# hackeeg-shield.net
KiCad netlist of a schematic drawn in EAGLE
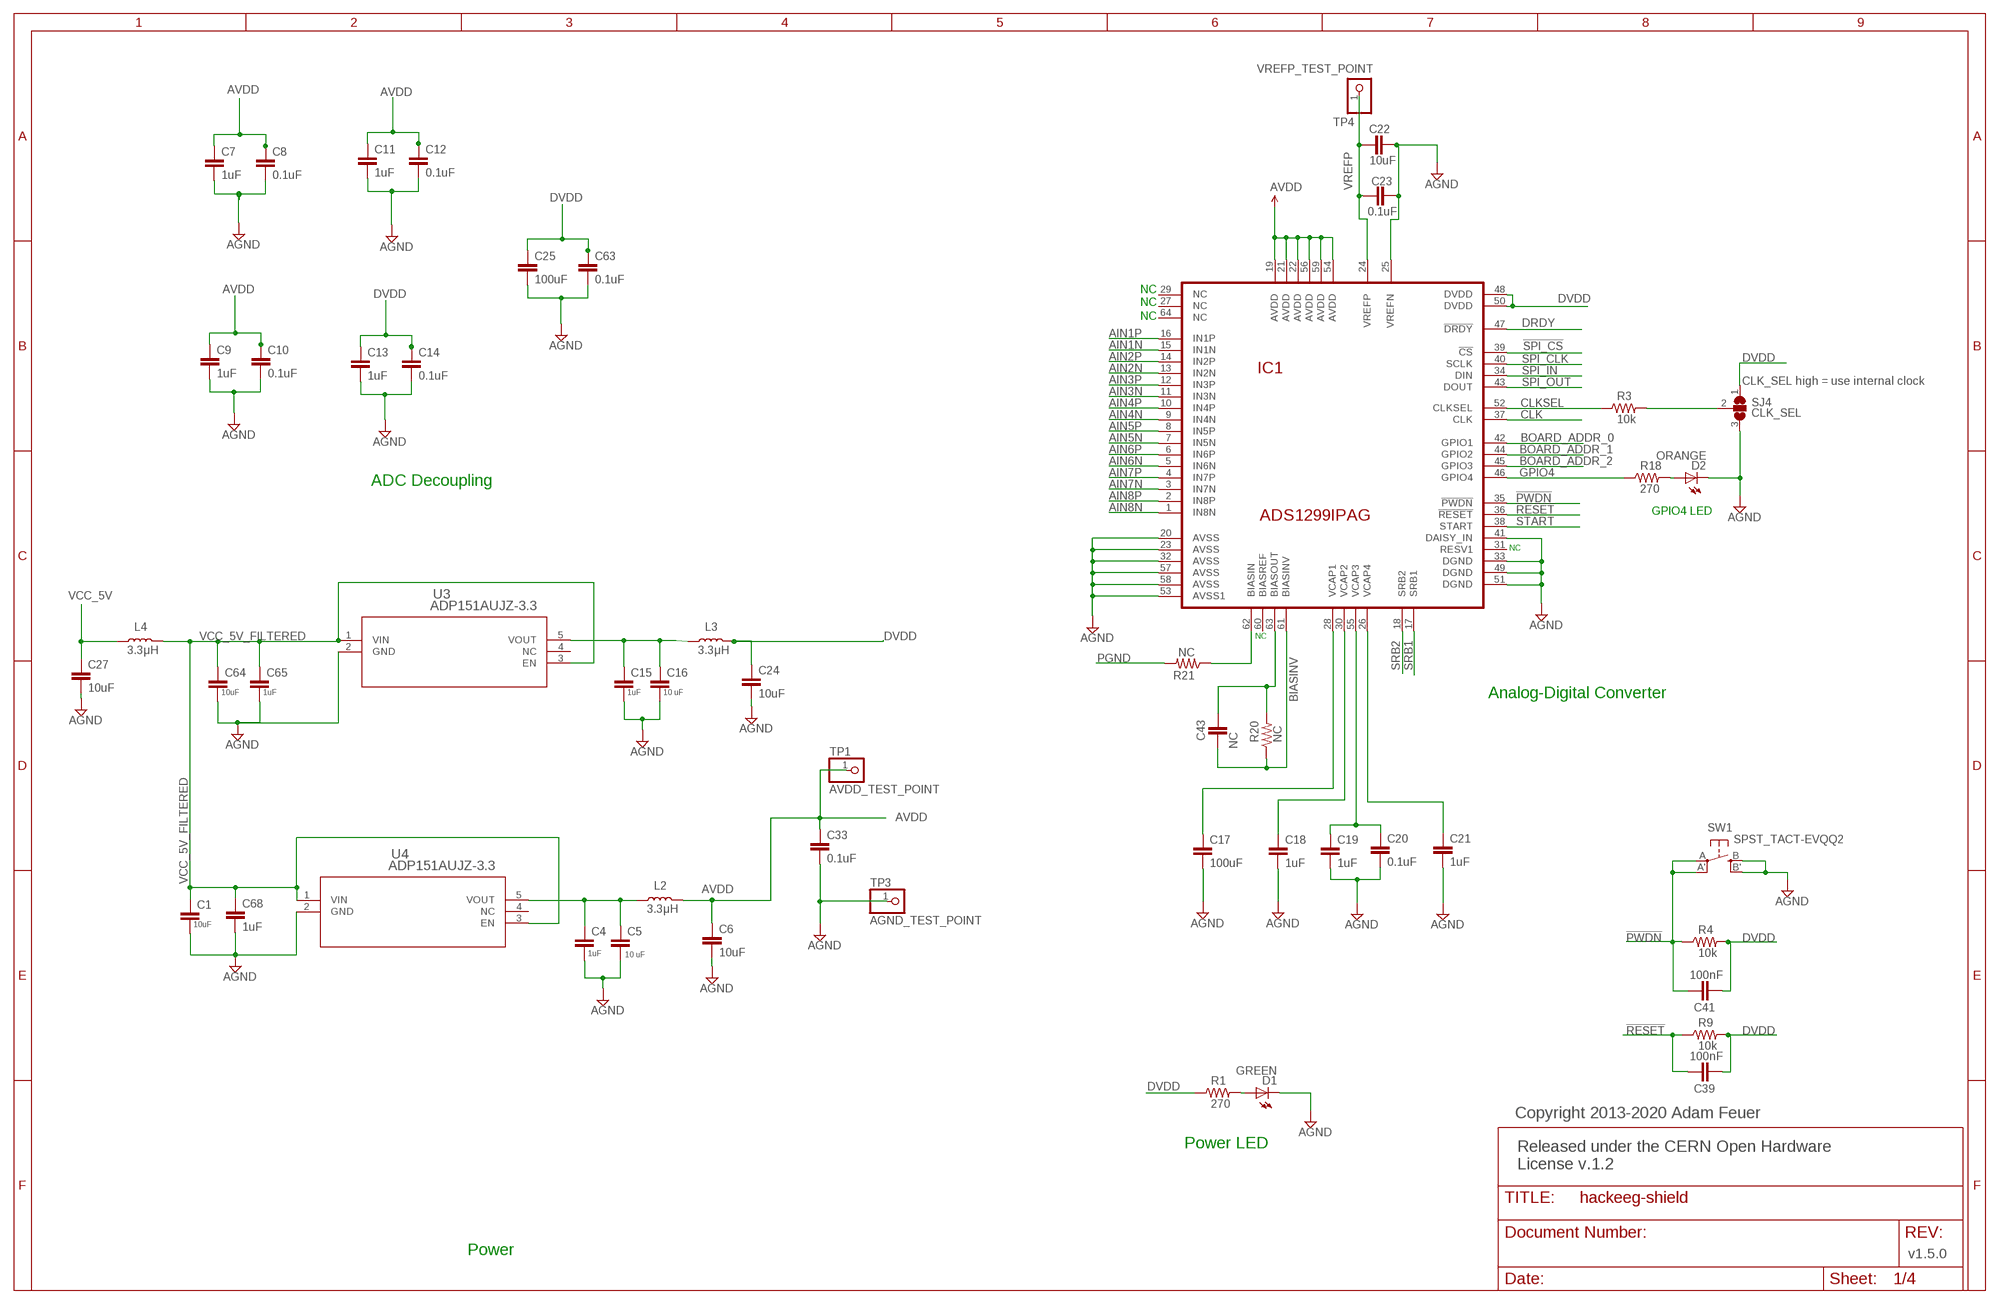
[diagram p0: schematic, sheet 1]
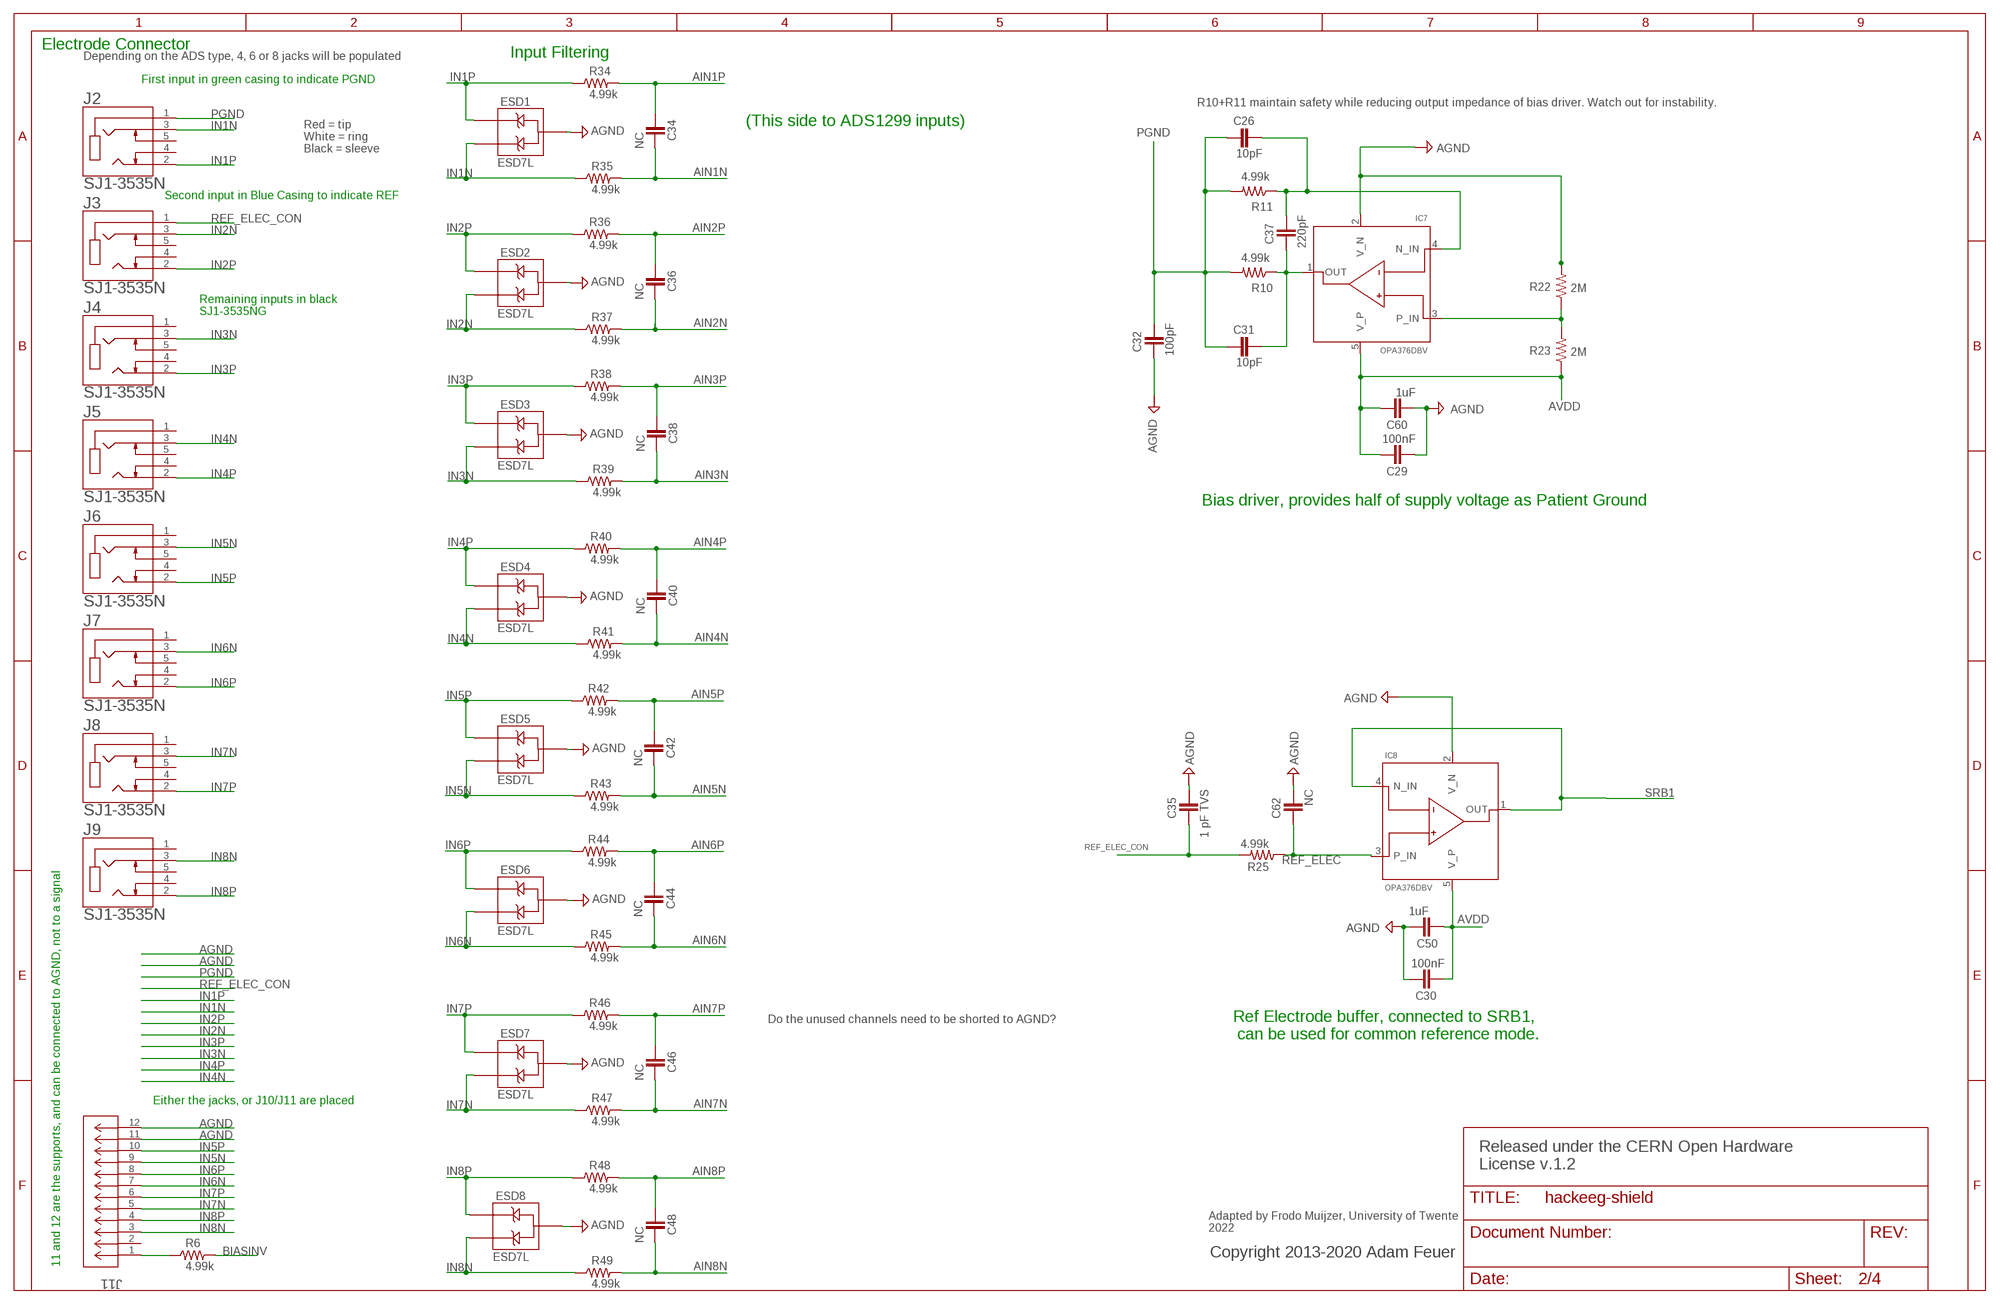
[diagram p1: schematic, sheet 2]
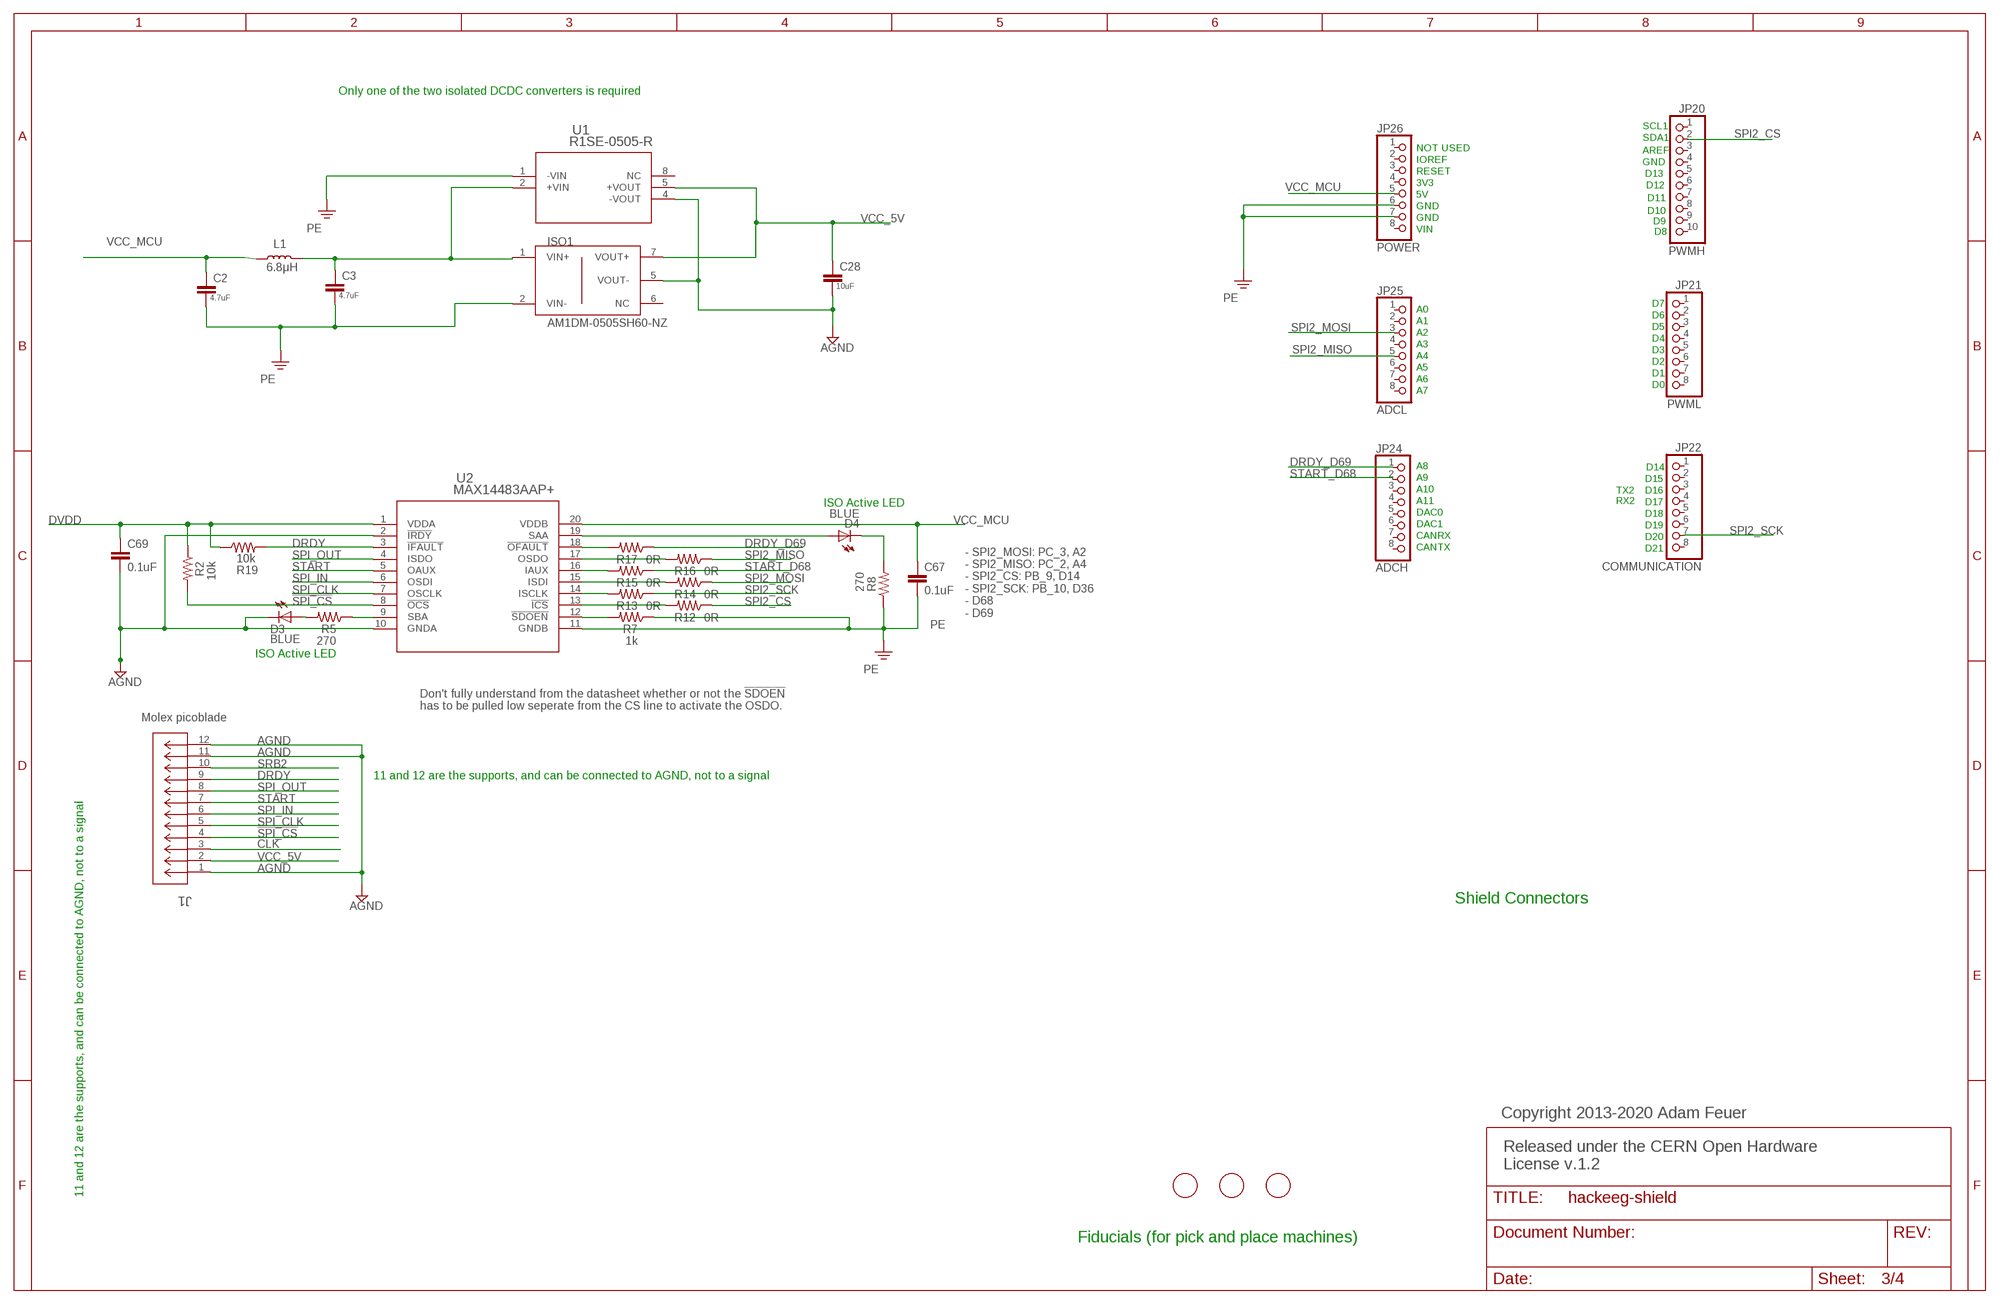
[diagram p2: schematic, sheet 3]
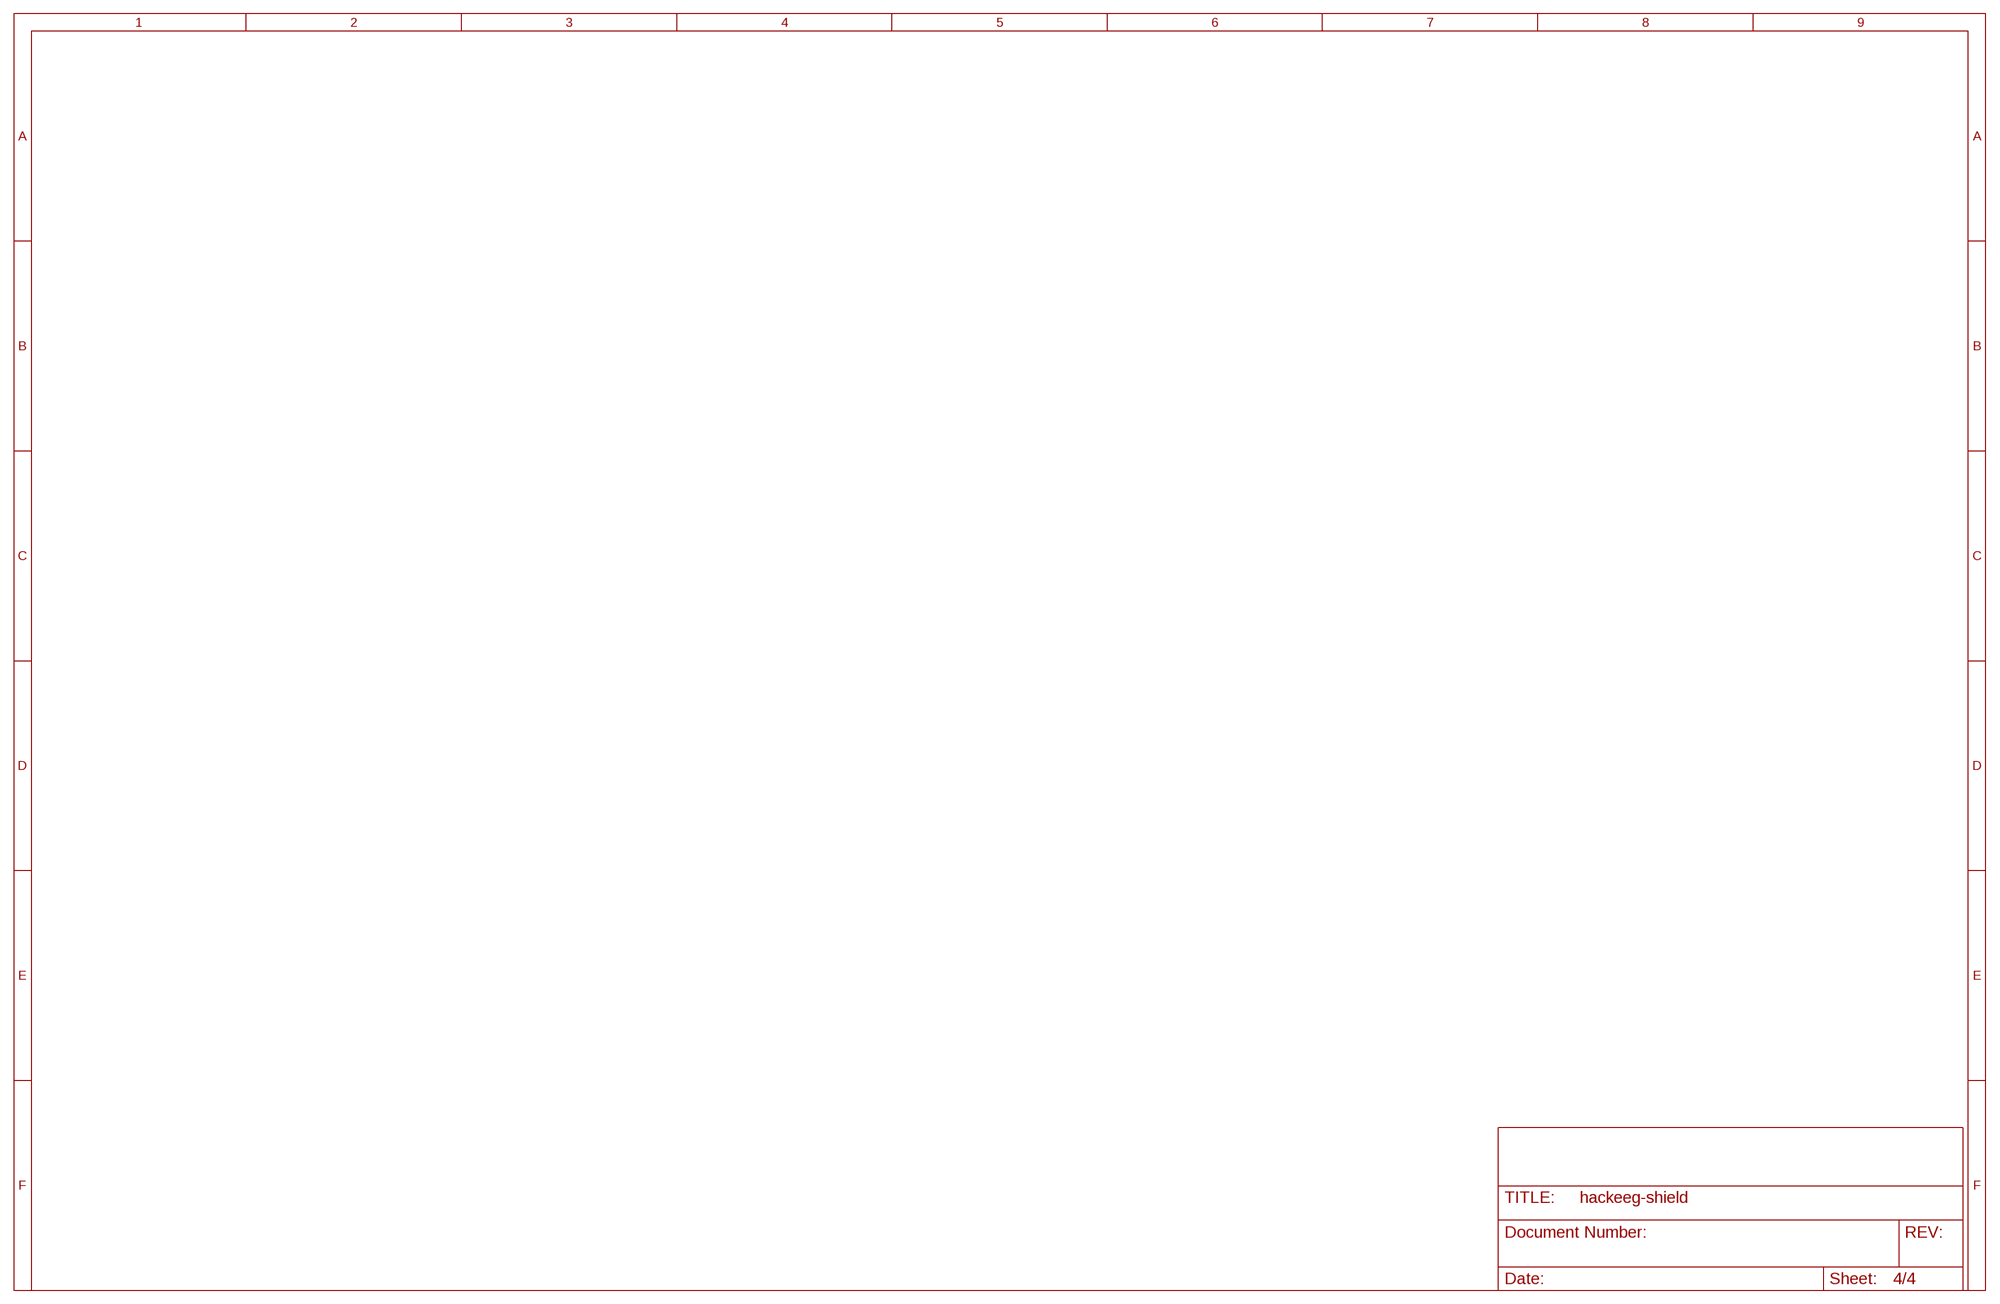
[diagram p3: schematic, sheet 4]

(export (version "E")
  (design (tool "Eeschema 10.0.6"))
  (components
    (comp (ref "C1")
      (value "10uF")
      (footprint "eagle-import:0603-CAP")
      (libsource (lib "eagle-import") (part "CAP0603-CAP"))
    )
    (comp (ref "C4")
      (value "1uF")
      (footprint "eagle-import:0603-CAP")
      (libsource (lib "eagle-import") (part "CAP0603-CAP"))
    )
    (comp (ref "C5")
      (value "10 uF")
      (footprint "eagle-import:0603-CAP")
      (libsource (lib "eagle-import") (part "CAP0603-CAP"))
    )
    (comp (ref "C6")
      (value "10uF")
      (footprint "eagle-import:0603-CAP")
      (libsource (lib "eagle-import") (part "CAP0603-CAP"))
    )
    (comp (ref "C7")
      (value "1uF")
      (footprint "eagle-import:0603-CAP")
      (libsource (lib "eagle-import") (part "CAP0603-CAP"))
    )
    (comp (ref "C8")
      (value "0.1uF")
      (footprint "eagle-import:0603-CAP")
      (libsource (lib "eagle-import") (part "CAP0603-CAP"))
    )
    (comp (ref "C9")
      (value "1uF")
      (footprint "eagle-import:0603-CAP")
      (libsource (lib "eagle-import") (part "CAP0603-CAP"))
    )
    (comp (ref "C10")
      (value "0.1uF")
      (footprint "eagle-import:0603-CAP")
      (libsource (lib "eagle-import") (part "CAP0603-CAP"))
    )
    (comp (ref "C11")
      (value "1uF")
      (footprint "eagle-import:0603-CAP")
      (libsource (lib "eagle-import") (part "CAP0603-CAP"))
    )
    (comp (ref "C12")
      (value "0.1uF")
      (footprint "eagle-import:0603-CAP")
      (libsource (lib "eagle-import") (part "CAP0603-CAP"))
    )
    (comp (ref "C13")
      (value "1uF")
      (footprint "eagle-import:0603-CAP")
      (libsource (lib "eagle-import") (part "CAP0603-CAP"))
    )
    (comp (ref "C14")
      (value "0.1uF")
      (footprint "eagle-import:0603-CAP")
      (libsource (lib "eagle-import") (part "CAP0603-CAP"))
    )
    (comp (ref "C15")
      (value "1uF")
      (footprint "eagle-import:0603-CAP")
      (libsource (lib "eagle-import") (part "CAP0603-CAP"))
    )
    (comp (ref "C16")
      (value "10 uF")
      (footprint "eagle-import:0603-CAP")
      (libsource (lib "eagle-import") (part "CAP0603-CAP"))
    )
    (comp (ref "C17")
      (value "100uF")
      (footprint "eagle-import:1210")
      (libsource (lib "eagle-import") (part "CAP1210"))
    )
    (comp (ref "C18")
      (value "1uF")
      (footprint "eagle-import:0603-CAP")
      (libsource (lib "eagle-import") (part "CAP0603-CAP"))
    )
    (comp (ref "C19")
      (value "1uF")
      (footprint "eagle-import:0603-CAP")
      (libsource (lib "eagle-import") (part "CAP0603-CAP"))
    )
    (comp (ref "C20")
      (value "0.1uF")
      (footprint "eagle-import:0603-CAP")
      (libsource (lib "eagle-import") (part "CAP0603-CAP"))
    )
    (comp (ref "C21")
      (value "1uF")
      (footprint "eagle-import:0603-CAP")
      (libsource (lib "eagle-import") (part "CAP0603-CAP"))
    )
    (comp (ref "C22")
      (value "10uF")
      (footprint "eagle-import:0603-CAP")
      (libsource (lib "eagle-import") (part "CAP0603-CAP"))
    )
    (comp (ref "C23")
      (value "0.1uF")
      (footprint "eagle-import:0603-CAP")
      (libsource (lib "eagle-import") (part "CAP0603-CAP"))
    )
    (comp (ref "C24")
      (value "10uF")
      (footprint "eagle-import:0603-CAP")
      (libsource (lib "eagle-import") (part "CAP0603-CAP"))
    )
    (comp (ref "C25")
      (value "100uF")
      (footprint "eagle-import:1210")
      (libsource (lib "eagle-import") (part "CAP1210"))
    )
    (comp (ref "C27")
      (value "10uF")
      (footprint "eagle-import:0603-CAP")
      (libsource (lib "eagle-import") (part "CAP0603-CAP"))
    )
    (comp (ref "C33")
      (value "0.1uF")
      (footprint "eagle-import:0603-CAP")
      (libsource (lib "eagle-import") (part "CAP0603-CAP"))
    )
    (comp (ref "C39")
      (value "100nF")
      (footprint "eagle-import:0603-CAP")
      (libsource (lib "eagle-import") (part "CAP0603-CAP"))
    )
    (comp (ref "C41")
      (value "100nF")
      (footprint "eagle-import:0603-CAP")
      (libsource (lib "eagle-import") (part "CAP0603-CAP"))
    )
    (comp (ref "C43")
      (value "NC")
      (footprint "eagle-import:0603-CAP")
      (libsource (lib "eagle-import") (part "CAP0603-CAP"))
    )
    (comp (ref "C63")
      (value "0.1uF")
      (footprint "eagle-import:0603-CAP")
      (libsource (lib "eagle-import") (part "CAP0603-CAP"))
    )
    (comp (ref "C64")
      (value "10uF")
      (footprint "eagle-import:0603-CAP")
      (libsource (lib "eagle-import") (part "CAP0603-CAP"))
    )
    (comp (ref "C65")
      (value "1uF")
      (footprint "eagle-import:0603-CAP")
      (libsource (lib "eagle-import") (part "CAP0603-CAP"))
    )
    (comp (ref "C68")
      (value "1uF")
      (footprint "eagle-import:0603-CAP")
      (libsource (lib "eagle-import") (part "CAP0603-CAP"))
    )
    (comp (ref "D1")
      (value "GREEN")
      (footprint "eagle-import:LED-1206")
      (libsource (lib "eagle-import") (part "LED-RED1206"))
    )
    (comp (ref "D2")
      (value "ORANGE")
      (footprint "eagle-import:LED-1206")
      (libsource (lib "eagle-import") (part "LED-WHITE"))
    )
    (comp (ref "IC1")
      (value "ADS1299IPAG")
      (footprint "eagle-import:TQFP64")
      (libsource (lib "eagle-import") (part "ADS1299PAG"))
    )
    (comp (ref "L2")
      (value "3.3μH")
      (footprint "eagle-import:0805-WIDE")
      (libsource (lib "eagle-import") (part "1.0μH-0805_WIDE-1.0μH-1.4A-0.07OHM-1.4MM_H"))
    )
    (comp (ref "L3")
      (value "3.3μH")
      (footprint "eagle-import:0805-WIDE")
      (libsource (lib "eagle-import") (part "1.0μH-0805_WIDE-1.0μH-1.4A-0.07OHM-1.4MM_H"))
    )
    (comp (ref "L4")
      (value "3.3μH")
      (footprint "eagle-import:0805-WIDE")
      (libsource (lib "eagle-import") (part "1.0μH-0805_WIDE-1.0μH-1.4A-0.07OHM-1.4MM_H"))
    )
    (comp (ref "R1")
      (value "270")
      (footprint "eagle-import:0603-RES")
      (libsource (lib "eagle-import") (part "RESISTOR0603-RES"))
    )
    (comp (ref "R3")
      (value "10k")
      (footprint "eagle-import:0603-RES")
      (libsource (lib "eagle-import") (part "RESISTOR0603-RES"))
    )
    (comp (ref "R4")
      (value "10k")
      (footprint "eagle-import:0603-RES")
      (libsource (lib "eagle-import") (part "RESISTOR0603-RES"))
    )
    (comp (ref "R9")
      (value "10k")
      (footprint "eagle-import:0603-RES")
      (libsource (lib "eagle-import") (part "RESISTOR0603-RES"))
    )
    (comp (ref "R18")
      (value "270")
      (footprint "eagle-import:0603-RES")
      (libsource (lib "eagle-import") (part "RESISTOR0603-RES"))
    )
    (comp (ref "R20")
      (value "NC")
      (footprint "eagle-import:0603-RES")
      (libsource (lib "eagle-import") (part "RESISTOR0603-RES"))
    )
    (comp (ref "R21")
      (value "NC")
      (footprint "eagle-import:0603-RES")
      (libsource (lib "eagle-import") (part "RESISTOR0603-RES"))
    )
    (comp (ref "SJ4")
      (value "CLK_SEL")
      (footprint "eagle-import:SJ_2")
      (libsource (lib "eagle-import") (part "SJ2W"))
    )
    (comp (ref "SW1")
      (value "SPST_TACT-EVQQ2")
      (footprint "eagle-import:EVQ-Q2")
      (libsource (lib "eagle-import") (part "SPST_TACT-EVQQ2"))
    )
    (comp (ref "TP1")
      (value "AVDD_TEST_POINT")
      (footprint "eagle-import:1X01")
      (libsource (lib "eagle-import") (part "PINHD-1X1"))
    )
    (comp (ref "TP3")
      (value "AGND_TEST_POINT")
      (footprint "eagle-import:1X01")
      (libsource (lib "eagle-import") (part "PINHD-1X1"))
    )
    (comp (ref "TP4")
      (value "VREFP_TEST_POINT")
      (footprint "eagle-import:1X01")
      (libsource (lib "eagle-import") (part "PINHD-1X1"))
    )
    (comp (ref "U3")
      (value "ADP151AUJZ-3.3")
      (footprint "eagle-import:UJ_5_ADI")
      (fields
        (field (name "MANUFACTURER_PART_NUMBER") "ADP151AUJZ-1.2-R7")
        (field (name "COPYRIGHT") "Copyright (C) 2022 Ultra Librarian. All rights reserved.")
      )
      (libsource (lib "eagle-import") (part "ADP151AUJZ-3.3"))
    )
    (comp (ref "U4")
      (value "ADP151AUJZ-3.3")
      (footprint "eagle-import:UJ_5_ADI")
      (fields
        (field (name "MANUFACTURER_PART_NUMBER") "ADP151AUJZ-1.2-R7")
        (field (name "COPYRIGHT") "Copyright (C) 2022 Ultra Librarian. All rights reserved.")
      )
      (libsource (lib "eagle-import") (part "ADP151AUJZ-3.3"))
    )
    (comp (ref "C26")
      (value "10pF")
      (footprint "eagle-import:0603-CAP")
      (libsource (lib "eagle-import") (part "CAP0603-CAP"))
    )
    (comp (ref "C29")
      (value "100nF")
      (footprint "eagle-import:0603-CAP")
      (libsource (lib "eagle-import") (part "CAP0603-CAP"))
    )
    (comp (ref "C30")
      (value "100nF")
      (footprint "eagle-import:0603-CAP")
      (libsource (lib "eagle-import") (part "CAP0603-CAP"))
    )
    (comp (ref "C31")
      (value "10pF")
      (footprint "eagle-import:0603-CAP")
      (libsource (lib "eagle-import") (part "CAP0603-CAP"))
    )
    (comp (ref "C32")
      (value "100pF")
      (footprint "eagle-import:0603-CAP")
      (libsource (lib "eagle-import") (part "CAP0603-CAP"))
    )
    (comp (ref "C34")
      (value "NC")
      (footprint "eagle-import:0603-CAP")
      (libsource (lib "eagle-import") (part "CAP0603-CAP"))
    )
    (comp (ref "C35")
      (value "1 pF TVS")
      (footprint "eagle-import:0603-CAP")
      (libsource (lib "eagle-import") (part "CAP0603-CAP"))
    )
    (comp (ref "C36")
      (value "NC")
      (footprint "eagle-import:0603-CAP")
      (libsource (lib "eagle-import") (part "CAP0603-CAP"))
    )
    (comp (ref "C37")
      (value "220pF")
      (footprint "eagle-import:0603-CAP")
      (libsource (lib "eagle-import") (part "CAP0603-CAP"))
    )
    (comp (ref "C38")
      (value "NC")
      (footprint "eagle-import:0603-CAP")
      (libsource (lib "eagle-import") (part "CAP0603-CAP"))
    )
    (comp (ref "C40")
      (value "NC")
      (footprint "eagle-import:0603-CAP")
      (libsource (lib "eagle-import") (part "CAP0603-CAP"))
    )
    (comp (ref "C42")
      (value "NC")
      (footprint "eagle-import:0603-CAP")
      (libsource (lib "eagle-import") (part "CAP0603-CAP"))
    )
    (comp (ref "C44")
      (value "NC")
      (footprint "eagle-import:0603-CAP")
      (libsource (lib "eagle-import") (part "CAP0603-CAP"))
    )
    (comp (ref "C46")
      (value "NC")
      (footprint "eagle-import:0603-CAP")
      (libsource (lib "eagle-import") (part "CAP0603-CAP"))
    )
    (comp (ref "C48")
      (value "NC")
      (footprint "eagle-import:0603-CAP")
      (libsource (lib "eagle-import") (part "CAP0603-CAP"))
    )
    (comp (ref "C50")
      (value "1uF")
      (footprint "eagle-import:0603-CAP")
      (libsource (lib "eagle-import") (part "CAP0603-CAP"))
    )
    (comp (ref "C60")
      (value "1uF")
      (footprint "eagle-import:0603-CAP")
      (libsource (lib "eagle-import") (part "CAP0603-CAP"))
    )
    (comp (ref "C62")
      (value "NC")
      (footprint "eagle-import:0603-CAP")
      (libsource (lib "eagle-import") (part "CAP0603-CAP"))
    )
    (comp (ref "ESD1")
      (value "ESD7L")
      (footprint "eagle-import:SOT-723")
      (fields (field (name "MF") "ON Semiconductor"))
      (libsource (lib "eagle-import") (part "ESD7L"))
    )
    (comp (ref "ESD2")
      (value "ESD7L")
      (footprint "eagle-import:SOT-723")
      (fields (field (name "MF") "ON Semiconductor"))
      (libsource (lib "eagle-import") (part "ESD7L"))
    )
    (comp (ref "ESD3")
      (value "ESD7L")
      (footprint "eagle-import:SOT-723")
      (fields (field (name "MF") "ON Semiconductor"))
      (libsource (lib "eagle-import") (part "ESD7L"))
    )
    (comp (ref "ESD4")
      (value "ESD7L")
      (footprint "eagle-import:SOT-723")
      (fields (field (name "MF") "ON Semiconductor"))
      (libsource (lib "eagle-import") (part "ESD7L"))
    )
    (comp (ref "ESD5")
      (value "ESD7L")
      (footprint "eagle-import:SOT-723")
      (fields (field (name "MF") "ON Semiconductor"))
      (libsource (lib "eagle-import") (part "ESD7L"))
    )
    (comp (ref "ESD6")
      (value "ESD7L")
      (footprint "eagle-import:SOT-723")
      (fields (field (name "MF") "ON Semiconductor"))
      (libsource (lib "eagle-import") (part "ESD7L"))
    )
    (comp (ref "ESD7")
      (value "ESD7L")
      (footprint "eagle-import:SOT-723")
      (fields (field (name "MF") "ON Semiconductor"))
      (libsource (lib "eagle-import") (part "ESD7L"))
    )
    (comp (ref "ESD8")
      (value "ESD7L")
      (footprint "eagle-import:SOT-723")
      (fields (field (name "MF") "ON Semiconductor"))
      (libsource (lib "eagle-import") (part "ESD7L"))
    )
    (comp (ref "IC7")
      (value "OPA376DBV")
      (footprint "eagle-import:SOT23-5")
      (libsource (lib "eagle-import") (part "OPA376DBV"))
    )
    (comp (ref "IC8")
      (value "OPA376DBV")
      (footprint "eagle-import:SOT23-5")
      (libsource (lib "eagle-import") (part "OPA376DBV"))
    )
    (comp (ref "J2")
      (value "SJ1-3535N")
      (footprint "eagle-import:CUI_SJ1-3535N")
      (fields (field (name "MANUFACTURER") "CUI"))
      (libsource (lib "eagle-import") (part "SJ1-3535N"))
    )
    (comp (ref "J3")
      (value "SJ1-3535N")
      (footprint "eagle-import:CUI_SJ1-3535N")
      (fields (field (name "MANUFACTURER") "CUI"))
      (libsource (lib "eagle-import") (part "SJ1-3535N"))
    )
    (comp (ref "J4")
      (value "SJ1-3535N")
      (footprint "eagle-import:CUI_SJ1-3535N")
      (fields (field (name "MANUFACTURER") "CUI"))
      (libsource (lib "eagle-import") (part "SJ1-3535N"))
    )
    (comp (ref "J5")
      (value "SJ1-3535N")
      (footprint "eagle-import:CUI_SJ1-3535N")
      (fields (field (name "MANUFACTURER") "CUI"))
      (libsource (lib "eagle-import") (part "SJ1-3535N"))
    )
    (comp (ref "J6")
      (value "SJ1-3535N")
      (footprint "eagle-import:CUI_SJ1-3535N")
      (fields (field (name "MANUFACTURER") "CUI"))
      (libsource (lib "eagle-import") (part "SJ1-3535N"))
    )
    (comp (ref "J7")
      (value "SJ1-3535N")
      (footprint "eagle-import:CUI_SJ1-3535N")
      (fields (field (name "MANUFACTURER") "CUI"))
      (libsource (lib "eagle-import") (part "SJ1-3535N"))
    )
    (comp (ref "J8")
      (value "SJ1-3535N")
      (footprint "eagle-import:CUI_SJ1-3535N")
      (fields (field (name "MANUFACTURER") "CUI"))
      (libsource (lib "eagle-import") (part "SJ1-3535N"))
    )
    (comp (ref "J9")
      (value "SJ1-3535N")
      (footprint "eagle-import:CUI_SJ1-3535N")
      (fields (field (name "MANUFACTURER") "CUI"))
      (libsource (lib "eagle-import") (part "SJ1-3535N"))
    )
    (comp (ref "J11")
      (value "533981071")
      (footprint "eagle-import:CON_533981071")
      (fields (field (name "COPYRIGHT") "Copyright (C) 2022 Ultra Librarian. All rights reserved."))
      (libsource (lib "eagle-import") (part "533981071"))
    )
    (comp (ref "R6")
      (value "4.99k")
      (footprint "eagle-import:0603-RES")
      (libsource (lib "eagle-import") (part "RESISTOR0603-RES"))
    )
    (comp (ref "R10")
      (value "4.99k")
      (footprint "eagle-import:0603-RES")
      (libsource (lib "eagle-import") (part "RESISTOR0603-RES"))
    )
    (comp (ref "R11")
      (value "4.99k")
      (footprint "eagle-import:0603-RES")
      (libsource (lib "eagle-import") (part "RESISTOR0603-RES"))
    )
    (comp (ref "R22")
      (value "2M")
      (footprint "eagle-import:0603-RES")
      (libsource (lib "eagle-import") (part "RESISTOR0603-RES"))
    )
    (comp (ref "R23")
      (value "2M")
      (footprint "eagle-import:0603-RES")
      (libsource (lib "eagle-import") (part "RESISTOR0603-RES"))
    )
    (comp (ref "R25")
      (value "4.99k")
      (footprint "eagle-import:0603-RES")
      (libsource (lib "eagle-import") (part "RESISTOR0603-RES"))
    )
    (comp (ref "R34")
      (value "4.99k")
      (footprint "eagle-import:0603-RES")
      (libsource (lib "eagle-import") (part "RESISTOR0603-RES"))
    )
    (comp (ref "R35")
      (value "4.99k")
      (footprint "eagle-import:0603-RES")
      (libsource (lib "eagle-import") (part "RESISTOR0603-RES"))
    )
    (comp (ref "R36")
      (value "4.99k")
      (footprint "eagle-import:0603-RES")
      (libsource (lib "eagle-import") (part "RESISTOR0603-RES"))
    )
    (comp (ref "R37")
      (value "4.99k")
      (footprint "eagle-import:0603-RES")
      (libsource (lib "eagle-import") (part "RESISTOR0603-RES"))
    )
    (comp (ref "R38")
      (value "4.99k")
      (footprint "eagle-import:0603-RES")
      (libsource (lib "eagle-import") (part "RESISTOR0603-RES"))
    )
    (comp (ref "R39")
      (value "4.99k")
      (footprint "eagle-import:0603-RES")
      (libsource (lib "eagle-import") (part "RESISTOR0603-RES"))
    )
    (comp (ref "R40")
      (value "4.99k")
      (footprint "eagle-import:0603-RES")
      (libsource (lib "eagle-import") (part "RESISTOR0603-RES"))
    )
    (comp (ref "R41")
      (value "4.99k")
      (footprint "eagle-import:0603-RES")
      (libsource (lib "eagle-import") (part "RESISTOR0603-RES"))
    )
    (comp (ref "R42")
      (value "4.99k")
      (footprint "eagle-import:0603-RES")
      (libsource (lib "eagle-import") (part "RESISTOR0603-RES"))
    )
    (comp (ref "R43")
      (value "4.99k")
      (footprint "eagle-import:0603-RES")
      (libsource (lib "eagle-import") (part "RESISTOR0603-RES"))
    )
    (comp (ref "R44")
      (value "4.99k")
      (footprint "eagle-import:0603-RES")
      (libsource (lib "eagle-import") (part "RESISTOR0603-RES"))
    )
    (comp (ref "R45")
      (value "4.99k")
      (footprint "eagle-import:0603-RES")
      (libsource (lib "eagle-import") (part "RESISTOR0603-RES"))
    )
    (comp (ref "R46")
      (value "4.99k")
      (footprint "eagle-import:0603-RES")
      (libsource (lib "eagle-import") (part "RESISTOR0603-RES"))
    )
    (comp (ref "R47")
      (value "4.99k")
      (footprint "eagle-import:0603-RES")
      (libsource (lib "eagle-import") (part "RESISTOR0603-RES"))
    )
    (comp (ref "R48")
      (value "4.99k")
      (footprint "eagle-import:0603-RES")
      (libsource (lib "eagle-import") (part "RESISTOR0603-RES"))
    )
    (comp (ref "R49")
      (value "4.99k")
      (footprint "eagle-import:0603-RES")
      (libsource (lib "eagle-import") (part "RESISTOR0603-RES"))
    )
    (comp (ref "C2")
      (value "4.7uF")
      (footprint "eagle-import:0603-CAP")
      (libsource (lib "eagle-import") (part "CAP0603-CAP"))
    )
    (comp (ref "C3")
      (value "4.7uF")
      (footprint "eagle-import:0603-CAP")
      (libsource (lib "eagle-import") (part "CAP0603-CAP"))
    )
    (comp (ref "C28")
      (value "10uF")
      (footprint "eagle-import:0603-CAP")
      (libsource (lib "eagle-import") (part "CAP0603-CAP"))
    )
    (comp (ref "C67")
      (value "0.1uF")
      (footprint "eagle-import:0603-CAP")
      (libsource (lib "eagle-import") (part "CAP0603-CAP"))
    )
    (comp (ref "C69")
      (value "0.1uF")
      (footprint "eagle-import:0603-CAP")
      (libsource (lib "eagle-import") (part "CAP0603-CAP"))
    )
    (comp (ref "D3")
      (value "BLUE")
      (footprint "eagle-import:LED-1206")
      (libsource (lib "eagle-import") (part "LED-WHITE"))
    )
    (comp (ref "D4")
      (value "BLUE")
      (footprint "eagle-import:LED-1206")
      (libsource (lib "eagle-import") (part "LED-WHITE"))
    )
    (comp (ref "ISO1")
      (value "AM1DM-0505SH60-NZ")
      (footprint "eagle-import:SIP1005W50P254L1965H1265Q7")
      (libsource (lib "eagle-import") (part "AM1DM-0505SH60-NZ"))
    )
    (comp (ref "J1")
      (value "533981071")
      (footprint "eagle-import:CON_533981071")
      (fields (field (name "COPYRIGHT") "Copyright (C) 2022 Ultra Librarian. All rights reserved."))
      (libsource (lib "eagle-import") (part "533981071"))
    )
    (comp (ref "JP20")
      (value "PWMH")
      (footprint "eagle-import:1X10")
      (libsource (lib "eagle-import") (part "PINHD-1X10"))
    )
    (comp (ref "JP21")
      (value "PWML")
      (footprint "eagle-import:1X08")
      (libsource (lib "eagle-import") (part "PINHD-1X8"))
    )
    (comp (ref "JP22")
      (value "COMMUNICATION")
      (footprint "eagle-import:1X08")
      (libsource (lib "eagle-import") (part "PINHD-1X8"))
    )
    (comp (ref "JP24")
      (value "ADCH")
      (footprint "eagle-import:1X08")
      (libsource (lib "eagle-import") (part "PINHD-1X8"))
    )
    (comp (ref "JP25")
      (value "ADCL")
      (footprint "eagle-import:1X08")
      (libsource (lib "eagle-import") (part "PINHD-1X8"))
    )
    (comp (ref "JP26")
      (value "POWER")
      (footprint "eagle-import:1X08")
      (libsource (lib "eagle-import") (part "PINHD-1X8"))
    )
    (comp (ref "L1")
      (value "6.8μH")
      (footprint "eagle-import:0805-WIDE")
      (fields (field (name "SPICEPREFIX") "L"))
      (libsource (lib "eagle-import") (part "1.0μH-0805_WIDE-1.0μH-1.4A-0.07OHM-1.4MM_H"))
    )
    (comp (ref "R2")
      (value "10k")
      (footprint "eagle-import:0603-RES")
      (libsource (lib "eagle-import") (part "RESISTOR0603-RES"))
    )
    (comp (ref "R5")
      (value "270")
      (footprint "eagle-import:0603-RES")
      (libsource (lib "eagle-import") (part "RESISTOR0603-RES"))
    )
    (comp (ref "R7")
      (value "1k")
      (footprint "eagle-import:0603-RES")
      (libsource (lib "eagle-import") (part "RESISTOR0603-RES"))
    )
    (comp (ref "R8")
      (value "270")
      (footprint "eagle-import:0603-RES")
      (libsource (lib "eagle-import") (part "RESISTOR0603-RES"))
    )
    (comp (ref "R12")
      (value "0R")
      (footprint "eagle-import:0603-RES")
      (libsource (lib "eagle-import") (part "RESISTOR0603-RES"))
    )
    (comp (ref "R13")
      (value "0R")
      (footprint "eagle-import:0603-RES")
      (libsource (lib "eagle-import") (part "RESISTOR0603-RES"))
    )
    (comp (ref "R14")
      (value "0R")
      (footprint "eagle-import:0603-RES")
      (libsource (lib "eagle-import") (part "RESISTOR0603-RES"))
    )
    (comp (ref "R15")
      (value "0R")
      (footprint "eagle-import:0603-RES")
      (libsource (lib "eagle-import") (part "RESISTOR0603-RES"))
    )
    (comp (ref "R16")
      (value "0R")
      (footprint "eagle-import:0603-RES")
      (libsource (lib "eagle-import") (part "RESISTOR0603-RES"))
    )
    (comp (ref "R17")
      (value "0R")
      (footprint "eagle-import:0603-RES")
      (libsource (lib "eagle-import") (part "RESISTOR0603-RES"))
    )
    (comp (ref "R19")
      (value "10k")
      (footprint "eagle-import:0603-RES")
      (libsource (lib "eagle-import") (part "RESISTOR0603-RES"))
    )
    (comp (ref "U$2")
      (value "FIDUCIAL")
      (footprint "eagle-import:FIDUCIAL_1MM")
      (libsource (lib "eagle-import") (part "FIDUCIAL"))
    )
    (comp (ref "U$5")
      (value "FIDUCIAL")
      (footprint "eagle-import:FIDUCIAL_1MM")
      (libsource (lib "eagle-import") (part "FIDUCIAL"))
    )
    (comp (ref "U$6")
      (value "FIDUCIAL")
      (footprint "eagle-import:FIDUCIAL_1MM")
      (libsource (lib "eagle-import") (part "FIDUCIAL"))
    )
    (comp (ref "U1")
      (value "R1SE-0505-R")
      (footprint "eagle-import:R1SE-0505-R_RCP")
      (fields (field (name "COPYRIGHT") "Copyright (C) 2022 Ultra Librarian. All rights reserved."))
      (libsource (lib "eagle-import") (part "R1SE-0505-R"))
    )
    (comp (ref "U2")
      (value "MAX14483AAP+")
      (footprint "eagle-import:21-0056C_20_MXM")
      (fields (field (name "COPYRIGHT") "Copyright (C) 2022 Ultra Librarian. All rights reserved."))
      (libsource (lib "eagle-import") (part "MAX14483AAP+"))
    )
  )
  (nets
    (net (code "1") (name "AGND") (class "Default")
      (node (ref "C1") (pin "2") (pinfunction "2_2") (pintype "passive"))
      (node (ref "C10") (pin "2") (pinfunction "2_2") (pintype "passive"))
      (node (ref "C11") (pin "2") (pinfunction "2_2") (pintype "passive"))
      (node (ref "C12") (pin "2") (pinfunction "2_2") (pintype "passive"))
      (node (ref "C13") (pin "2") (pinfunction "2_2") (pintype "passive"))
      (node (ref "C14") (pin "2") (pinfunction "2_2") (pintype "passive"))
      (node (ref "C15") (pin "2") (pinfunction "2_2") (pintype "passive"))
      (node (ref "C16") (pin "2") (pinfunction "2_2") (pintype "passive"))
      (node (ref "C17") (pin "2") (pinfunction "2_2") (pintype "passive"))
      (node (ref "C18") (pin "2") (pinfunction "2_2") (pintype "passive"))
      (node (ref "C19") (pin "2") (pinfunction "2_2") (pintype "passive"))
      (node (ref "C20") (pin "2") (pinfunction "2_2") (pintype "passive"))
      (node (ref "C21") (pin "2") (pinfunction "2_2") (pintype "passive"))
      (node (ref "C22") (pin "2") (pinfunction "2_2") (pintype "passive"))
      (node (ref "C23") (pin "2") (pinfunction "2_2") (pintype "passive"))
      (node (ref "C24") (pin "2") (pinfunction "2_2") (pintype "passive"))
      (node (ref "C25") (pin "2") (pinfunction "2_2") (pintype "passive"))
      (node (ref "C27") (pin "2") (pinfunction "2_2") (pintype "passive"))
      (node (ref "C28") (pin "2") (pinfunction "2_2") (pintype "passive"))
      (node (ref "C29") (pin "2") (pinfunction "2_2") (pintype "passive"))
      (node (ref "C30") (pin "1") (pinfunction "1_1") (pintype "passive"))
      (node (ref "C32") (pin "1") (pinfunction "1_1") (pintype "passive"))
      (node (ref "C33") (pin "2") (pinfunction "2_2") (pintype "passive"))
      (node (ref "C35") (pin "2") (pinfunction "2_2") (pintype "passive"))
      (node (ref "C4") (pin "2") (pinfunction "2_2") (pintype "passive"))
      (node (ref "C5") (pin "2") (pinfunction "2_2") (pintype "passive"))
      (node (ref "C50") (pin "2") (pinfunction "2_2") (pintype "passive"))
      (node (ref "C6") (pin "2") (pinfunction "2_2") (pintype "passive"))
      (node (ref "C60") (pin "2") (pinfunction "2_2") (pintype "passive"))
      (node (ref "C62") (pin "2") (pinfunction "2_2") (pintype "passive"))
      (node (ref "C63") (pin "2") (pinfunction "2_2") (pintype "passive"))
      (node (ref "C64") (pin "2") (pinfunction "2_2") (pintype "passive"))
      (node (ref "C65") (pin "2") (pinfunction "2_2") (pintype "passive"))
      (node (ref "C68") (pin "2") (pinfunction "2_2") (pintype "passive"))
      (node (ref "C69") (pin "2") (pinfunction "2_2") (pintype "passive"))
      (node (ref "C7") (pin "2") (pinfunction "2_2") (pintype "passive"))
      (node (ref "C8") (pin "2") (pinfunction "2_2") (pintype "passive"))
      (node (ref "C9") (pin "2") (pinfunction "2_2") (pintype "passive"))
      (node (ref "D1") (pin "C") (pinfunction "C_C") (pintype "passive"))
      (node (ref "D2") (pin "C") (pinfunction "C_C") (pintype "passive"))
      (node (ref "D3") (pin "C") (pinfunction "C_C") (pintype "passive"))
      (node (ref "ESD1") (pin "P$3") (pinfunction "P$3_P$3") (pintype "bidirectional"))
      (node (ref "ESD2") (pin "P$3") (pinfunction "P$3_P$3") (pintype "bidirectional"))
      (node (ref "ESD3") (pin "P$3") (pinfunction "P$3_P$3") (pintype "bidirectional"))
      (node (ref "ESD4") (pin "P$3") (pinfunction "P$3_P$3") (pintype "bidirectional"))
      (node (ref "ESD5") (pin "P$3") (pinfunction "P$3_P$3") (pintype "bidirectional"))
      (node (ref "ESD6") (pin "P$3") (pinfunction "P$3_P$3") (pintype "bidirectional"))
      (node (ref "ESD7") (pin "P$3") (pinfunction "P$3_P$3") (pintype "bidirectional"))
      (node (ref "ESD8") (pin "P$3") (pinfunction "P$3_P$3") (pintype "bidirectional"))
      (node (ref "IC1") (pin "20") (pinfunction "AVSS_20") (pintype "power_in"))
      (node (ref "IC1") (pin "23") (pinfunction "AVSS_23") (pintype "power_in"))
      (node (ref "IC1") (pin "25") (pinfunction "VREFN_25") (pintype "bidirectional"))
      (node (ref "IC1") (pin "32") (pinfunction "AVSS_32") (pintype "power_in"))
      (node (ref "IC1") (pin "33") (pinfunction "DGND_33") (pintype "power_in"))
      (node (ref "IC1") (pin "41") (pinfunction "DAISY_IN_41") (pintype "input"))
      (node (ref "IC1") (pin "49") (pinfunction "DGND_49") (pintype "power_in"))
      (node (ref "IC1") (pin "51") (pinfunction "DGND_51") (pintype "power_in"))
      (node (ref "IC1") (pin "53") (pinfunction "AVSS1_53") (pintype "power_in"))
      (node (ref "IC1") (pin "57") (pinfunction "AVSS_57") (pintype "power_in"))
      (node (ref "IC1") (pin "58") (pinfunction "AVSS_58") (pintype "power_in"))
      (node (ref "IC7") (pin "2") (pinfunction "V_N_2") (pintype "bidirectional"))
      (node (ref "IC8") (pin "2") (pinfunction "V_N_2") (pintype "bidirectional"))
      (node (ref "ISO1") (pin "5") (pinfunction "VOUT-_5") (pintype "output"))
      (node (ref "J1") (pin "1") (pinfunction "1_1") (pintype "passive"))
      (node (ref "J1") (pin "11") (pinfunction "11_11") (pintype "passive"))
      (node (ref "J1") (pin "12") (pinfunction "12_12") (pintype "passive"))
      (node (ref "J11") (pin "11") (pinfunction "11_11") (pintype "passive"))
      (node (ref "J11") (pin "12") (pinfunction "12_12") (pintype "passive"))
      (node (ref "R22") (pin "2") (pinfunction "2_2") (pintype "passive"))
      (node (ref "SJ4") (pin "3") (pinfunction "3_3") (pintype "passive"))
      (node (ref "SW1") (pin "B") (pinfunction "S_B") (pintype "passive"))
      (node (ref "SW1") (pin "B'") (pinfunction "S1_B'") (pintype "passive"))
      (node (ref "TP3") (pin "1") (pinfunction "1_1") (pintype "passive"))
      (node (ref "U1") (pin "4") (pinfunction "-VOUT_4") (pintype "passive"))
      (node (ref "U2") (pin "10") (pinfunction "GNDA_10") (pintype "passive"))
      (node (ref "U2") (pin "2") (pinfunction "~{IRDY}_2") (pintype "passive"))
      (node (ref "U3") (pin "2") (pinfunction "GND_2") (pintype "power_in"))
      (node (ref "U4") (pin "2") (pinfunction "GND_2") (pintype "power_in"))
    )
    (net (code "2") (name "AIN1N") (class "Default")
      (node (ref "C34") (pin "2") (pinfunction "2_2") (pintype "passive"))
      (node (ref "IC1") (pin "15") (pinfunction "IN1N_15") (pintype "input"))
      (node (ref "R35") (pin "2") (pinfunction "2_2") (pintype "passive"))
    )
    (net (code "3") (name "AIN1P") (class "Default")
      (node (ref "C34") (pin "1") (pinfunction "1_1") (pintype "passive"))
      (node (ref "IC1") (pin "16") (pinfunction "IN1P_16") (pintype "input"))
      (node (ref "R34") (pin "2") (pinfunction "2_2") (pintype "passive"))
    )
    (net (code "4") (name "AIN2N") (class "Default")
      (node (ref "C36") (pin "2") (pinfunction "2_2") (pintype "passive"))
      (node (ref "IC1") (pin "13") (pinfunction "IN2N_13") (pintype "input"))
      (node (ref "R37") (pin "2") (pinfunction "2_2") (pintype "passive"))
    )
    (net (code "5") (name "AIN2P") (class "Default")
      (node (ref "C36") (pin "1") (pinfunction "1_1") (pintype "passive"))
      (node (ref "IC1") (pin "14") (pinfunction "IN2P_14") (pintype "input"))
      (node (ref "R36") (pin "2") (pinfunction "2_2") (pintype "passive"))
    )
    (net (code "6") (name "AIN3N") (class "Default")
      (node (ref "C38") (pin "2") (pinfunction "2_2") (pintype "passive"))
      (node (ref "IC1") (pin "11") (pinfunction "IN3N_11") (pintype "input"))
      (node (ref "R39") (pin "2") (pinfunction "2_2") (pintype "passive"))
    )
    (net (code "7") (name "AIN3P") (class "Default")
      (node (ref "C38") (pin "1") (pinfunction "1_1") (pintype "passive"))
      (node (ref "IC1") (pin "12") (pinfunction "IN3P_12") (pintype "input"))
      (node (ref "R38") (pin "2") (pinfunction "2_2") (pintype "passive"))
    )
    (net (code "8") (name "AIN4N") (class "Default")
      (node (ref "C40") (pin "2") (pinfunction "2_2") (pintype "passive"))
      (node (ref "IC1") (pin "9") (pinfunction "IN4N_9") (pintype "input"))
      (node (ref "R41") (pin "2") (pinfunction "2_2") (pintype "passive"))
    )
    (net (code "9") (name "AIN4P") (class "Default")
      (node (ref "C40") (pin "1") (pinfunction "1_1") (pintype "passive"))
      (node (ref "IC1") (pin "10") (pinfunction "IN4P_10") (pintype "input"))
      (node (ref "R40") (pin "2") (pinfunction "2_2") (pintype "passive"))
    )
    (net (code "10") (name "AIN5N") (class "Default")
      (node (ref "C42") (pin "2") (pinfunction "2_2") (pintype "passive"))
      (node (ref "IC1") (pin "7") (pinfunction "IN5N_7") (pintype "input"))
      (node (ref "R43") (pin "2") (pinfunction "2_2") (pintype "passive"))
    )
    (net (code "11") (name "AIN5P") (class "Default")
      (node (ref "C42") (pin "1") (pinfunction "1_1") (pintype "passive"))
      (node (ref "IC1") (pin "8") (pinfunction "IN5P_8") (pintype "input"))
      (node (ref "R42") (pin "2") (pinfunction "2_2") (pintype "passive"))
    )
    (net (code "12") (name "AIN6N") (class "Default")
      (node (ref "C44") (pin "2") (pinfunction "2_2") (pintype "passive"))
      (node (ref "IC1") (pin "5") (pinfunction "IN6N_5") (pintype "input"))
      (node (ref "R45") (pin "2") (pinfunction "2_2") (pintype "passive"))
    )
    (net (code "13") (name "AIN6P") (class "Default")
      (node (ref "C44") (pin "1") (pinfunction "1_1") (pintype "passive"))
      (node (ref "IC1") (pin "6") (pinfunction "IN6P_6") (pintype "input"))
      (node (ref "R44") (pin "2") (pinfunction "2_2") (pintype "passive"))
    )
    (net (code "14") (name "AIN7N") (class "Default")
      (node (ref "C46") (pin "2") (pinfunction "2_2") (pintype "passive"))
      (node (ref "IC1") (pin "3") (pinfunction "IN7N_3") (pintype "input"))
      (node (ref "R47") (pin "2") (pinfunction "2_2") (pintype "passive"))
    )
    (net (code "15") (name "AIN7P") (class "Default")
      (node (ref "C46") (pin "1") (pinfunction "1_1") (pintype "passive"))
      (node (ref "IC1") (pin "4") (pinfunction "IN7P_4") (pintype "input"))
      (node (ref "R46") (pin "2") (pinfunction "2_2") (pintype "passive"))
    )
    (net (code "16") (name "AIN8N") (class "Default")
      (node (ref "C48") (pin "2") (pinfunction "2_2") (pintype "passive"))
      (node (ref "IC1") (pin "1") (pinfunction "IN8N_1") (pintype "input"))
      (node (ref "R49") (pin "2") (pinfunction "2_2") (pintype "passive"))
    )
    (net (code "17") (name "AIN8P") (class "Default")
      (node (ref "C48") (pin "1") (pinfunction "1_1") (pintype "passive"))
      (node (ref "IC1") (pin "2") (pinfunction "IN8P_2") (pintype "input"))
      (node (ref "R48") (pin "2") (pinfunction "2_2") (pintype "passive"))
    )
    (net (code "18") (name "AVDD") (class "Default")
      (node (ref "C10") (pin "1") (pinfunction "1_1") (pintype "passive"))
      (node (ref "C11") (pin "1") (pinfunction "1_1") (pintype "passive"))
      (node (ref "C12") (pin "1") (pinfunction "1_1") (pintype "passive"))
      (node (ref "C29") (pin "1") (pinfunction "1_1") (pintype "passive"))
      (node (ref "C30") (pin "2") (pinfunction "2_2") (pintype "passive"))
      (node (ref "C33") (pin "1") (pinfunction "1_1") (pintype "passive"))
      (node (ref "C50") (pin "1") (pinfunction "1_1") (pintype "passive"))
      (node (ref "C6") (pin "1") (pinfunction "1_1") (pintype "passive"))
      (node (ref "C60") (pin "1") (pinfunction "1_1") (pintype "passive"))
      (node (ref "C7") (pin "1") (pinfunction "1_1") (pintype "passive"))
      (node (ref "C8") (pin "1") (pinfunction "1_1") (pintype "passive"))
      (node (ref "C9") (pin "1") (pinfunction "1_1") (pintype "passive"))
      (node (ref "IC1") (pin "19") (pinfunction "AVDD_19") (pintype "power_in"))
      (node (ref "IC1") (pin "21") (pinfunction "AVDD_21") (pintype "power_in"))
      (node (ref "IC1") (pin "22") (pinfunction "AVDD_22") (pintype "power_in"))
      (node (ref "IC1") (pin "54") (pinfunction "AVDD_54") (pintype "power_in"))
      (node (ref "IC1") (pin "56") (pinfunction "AVDD_56") (pintype "power_in"))
      (node (ref "IC1") (pin "59") (pinfunction "AVDD_59") (pintype "power_in"))
      (node (ref "IC7") (pin "5") (pinfunction "V_P_5") (pintype "bidirectional"))
      (node (ref "IC8") (pin "5") (pinfunction "V_P_5") (pintype "bidirectional"))
      (node (ref "L2") (pin "2") (pinfunction "2_2") (pintype "passive"))
      (node (ref "R23") (pin "1") (pinfunction "1_1") (pintype "passive"))
      (node (ref "TP1") (pin "1") (pinfunction "1_1") (pintype "passive"))
    )
    (net (code "19") (name "BIASINV") (class "Default")
      (node (ref "C43") (pin "2") (pinfunction "2_2") (pintype "passive"))
      (node (ref "IC1") (pin "61") (pinfunction "BIASINV_61") (pintype "bidirectional"))
      (node (ref "R20") (pin "1") (pinfunction "1_1") (pintype "passive"))
      (node (ref "R6") (pin "2") (pinfunction "2_2") (pintype "passive"))
    )
    (net (code "20") (name "BOARD_ADDR_0") (class "Default")
      (node (ref "IC1") (pin "42") (pinfunction "GPIO1_42") (pintype "bidirectional"))
    )
    (net (code "21") (name "BOARD_ADDR_1") (class "Default")
      (node (ref "IC1") (pin "44") (pinfunction "GPIO2_44") (pintype "bidirectional"))
    )
    (net (code "22") (name "BOARD_ADDR_2") (class "Default")
      (node (ref "IC1") (pin "45") (pinfunction "GPIO3_45") (pintype "bidirectional"))
    )
    (net (code "23") (name "CLK") (class "Default")
      (node (ref "IC1") (pin "37") (pinfunction "CLK_37") (pintype "input"))
      (node (ref "J1") (pin "3") (pinfunction "3_3") (pintype "passive"))
    )
    (net (code "24") (name "CLKSEL") (class "Default")
      (node (ref "IC1") (pin "52") (pinfunction "CLKSEL_52") (pintype "input"))
      (node (ref "R3") (pin "1") (pinfunction "1_1") (pintype "passive"))
    )
    (net (code "25") (name "DRDY") (class "Default")
      (node (ref "IC1") (pin "47") (pinfunction "~{DRDY}_47") (pintype "output"))
      (node (ref "J1") (pin "9") (pinfunction "9_9") (pintype "passive"))
      (node (ref "R19") (pin "2") (pinfunction "2_2") (pintype "passive"))
      (node (ref "U2") (pin "3") (pinfunction "~{IFAULT}_3") (pintype "passive"))
    )
    (net (code "26") (name "DRDY_D69") (class "Default")
      (node (ref "JP24") (pin "1") (pinfunction "1_1") (pintype "passive"))
      (node (ref "R17") (pin "1") (pinfunction "1_1") (pintype "passive"))
    )
    (net (code "27") (name "DVDD") (class "Default")
      (node (ref "C13") (pin "1") (pinfunction "1_1") (pintype "passive"))
      (node (ref "C14") (pin "1") (pinfunction "1_1") (pintype "passive"))
      (node (ref "C24") (pin "1") (pinfunction "1_1") (pintype "passive"))
      (node (ref "C25") (pin "1") (pinfunction "1_1") (pintype "passive"))
      (node (ref "C39") (pin "2") (pinfunction "2_2") (pintype "passive"))
      (node (ref "C41") (pin "2") (pinfunction "2_2") (pintype "passive"))
      (node (ref "C63") (pin "1") (pinfunction "1_1") (pintype "passive"))
      (node (ref "C69") (pin "1") (pinfunction "1_1") (pintype "passive"))
      (node (ref "IC1") (pin "48") (pinfunction "DVDD_48") (pintype "power_in"))
      (node (ref "IC1") (pin "50") (pinfunction "DVDD_50") (pintype "power_in"))
      (node (ref "L3") (pin "2") (pinfunction "2_2") (pintype "passive"))
      (node (ref "R1") (pin "1") (pinfunction "1_1") (pintype "passive"))
      (node (ref "R19") (pin "1") (pinfunction "1_1") (pintype "passive"))
      (node (ref "R2") (pin "1") (pinfunction "1_1") (pintype "passive"))
      (node (ref "R4") (pin "2") (pinfunction "2_2") (pintype "passive"))
      (node (ref "R9") (pin "2") (pinfunction "2_2") (pintype "passive"))
      (node (ref "SJ4") (pin "1") (pinfunction "1_1") (pintype "passive"))
      (node (ref "U2") (pin "1") (pinfunction "VDDA_1") (pintype "power_in"))
    )
    (net (code "28") (name "GPIO4") (class "Default")
      (node (ref "IC1") (pin "46") (pinfunction "GPIO4_46") (pintype "bidirectional"))
      (node (ref "R18") (pin "1") (pinfunction "1_1") (pintype "passive"))
    )
    (net (code "29") (name "IN1N") (class "Default")
      (node (ref "ESD1") (pin "P$2") (pinfunction "P$2_P$2") (pintype "bidirectional"))
      (node (ref "J2") (pin "3") (pinfunction "3_3") (pintype "passive"))
      (node (ref "R35") (pin "1") (pinfunction "1_1") (pintype "passive"))
    )
    (net (code "30") (name "IN1P") (class "Default")
      (node (ref "ESD1") (pin "P$1") (pinfunction "P$1_P$1") (pintype "bidirectional"))
      (node (ref "J2") (pin "2") (pinfunction "2_2") (pintype "passive"))
      (node (ref "R34") (pin "1") (pinfunction "1_1") (pintype "passive"))
    )
    (net (code "31") (name "IN2N") (class "Default")
      (node (ref "ESD2") (pin "P$2") (pinfunction "P$2_P$2") (pintype "bidirectional"))
      (node (ref "J3") (pin "3") (pinfunction "3_3") (pintype "passive"))
      (node (ref "R37") (pin "1") (pinfunction "1_1") (pintype "passive"))
    )
    (net (code "32") (name "IN2P") (class "Default")
      (node (ref "ESD2") (pin "P$1") (pinfunction "P$1_P$1") (pintype "bidirectional"))
      (node (ref "J3") (pin "2") (pinfunction "2_2") (pintype "passive"))
      (node (ref "R36") (pin "1") (pinfunction "1_1") (pintype "passive"))
    )
    (net (code "33") (name "IN3N") (class "Default")
      (node (ref "ESD3") (pin "P$2") (pinfunction "P$2_P$2") (pintype "bidirectional"))
      (node (ref "J4") (pin "3") (pinfunction "3_3") (pintype "passive"))
      (node (ref "R39") (pin "1") (pinfunction "1_1") (pintype "passive"))
    )
    (net (code "34") (name "IN3P") (class "Default")
      (node (ref "ESD3") (pin "P$1") (pinfunction "P$1_P$1") (pintype "bidirectional"))
      (node (ref "J4") (pin "2") (pinfunction "2_2") (pintype "passive"))
      (node (ref "R38") (pin "1") (pinfunction "1_1") (pintype "passive"))
    )
    (net (code "35") (name "IN4N") (class "Default")
      (node (ref "ESD4") (pin "P$2") (pinfunction "P$2_P$2") (pintype "bidirectional"))
      (node (ref "J5") (pin "3") (pinfunction "3_3") (pintype "passive"))
      (node (ref "R41") (pin "1") (pinfunction "1_1") (pintype "passive"))
    )
    (net (code "36") (name "IN4P") (class "Default")
      (node (ref "ESD4") (pin "P$1") (pinfunction "P$1_P$1") (pintype "bidirectional"))
      (node (ref "J5") (pin "2") (pinfunction "2_2") (pintype "passive"))
      (node (ref "R40") (pin "1") (pinfunction "1_1") (pintype "passive"))
    )
    (net (code "37") (name "IN5N") (class "Default")
      (node (ref "ESD5") (pin "P$2") (pinfunction "P$2_P$2") (pintype "bidirectional"))
      (node (ref "J11") (pin "9") (pinfunction "9_9") (pintype "passive"))
      (node (ref "J6") (pin "3") (pinfunction "3_3") (pintype "passive"))
      (node (ref "R43") (pin "1") (pinfunction "1_1") (pintype "passive"))
    )
    (net (code "38") (name "IN5P") (class "Default")
      (node (ref "ESD5") (pin "P$1") (pinfunction "P$1_P$1") (pintype "bidirectional"))
      (node (ref "J11") (pin "10") (pinfunction "10_10") (pintype "passive"))
      (node (ref "J6") (pin "2") (pinfunction "2_2") (pintype "passive"))
      (node (ref "R42") (pin "1") (pinfunction "1_1") (pintype "passive"))
    )
    (net (code "39") (name "IN6N") (class "Default")
      (node (ref "ESD6") (pin "P$2") (pinfunction "P$2_P$2") (pintype "bidirectional"))
      (node (ref "J11") (pin "7") (pinfunction "7_7") (pintype "passive"))
      (node (ref "J7") (pin "3") (pinfunction "3_3") (pintype "passive"))
      (node (ref "R45") (pin "1") (pinfunction "1_1") (pintype "passive"))
    )
    (net (code "40") (name "IN6P") (class "Default")
      (node (ref "ESD6") (pin "P$1") (pinfunction "P$1_P$1") (pintype "bidirectional"))
      (node (ref "J11") (pin "8") (pinfunction "8_8") (pintype "passive"))
      (node (ref "J7") (pin "2") (pinfunction "2_2") (pintype "passive"))
      (node (ref "R44") (pin "1") (pinfunction "1_1") (pintype "passive"))
    )
    (net (code "41") (name "IN7N") (class "Default")
      (node (ref "ESD7") (pin "P$2") (pinfunction "P$2_P$2") (pintype "bidirectional"))
      (node (ref "J11") (pin "5") (pinfunction "5_5") (pintype "passive"))
      (node (ref "J8") (pin "3") (pinfunction "3_3") (pintype "passive"))
      (node (ref "R47") (pin "1") (pinfunction "1_1") (pintype "passive"))
    )
    (net (code "42") (name "IN7P") (class "Default")
      (node (ref "ESD7") (pin "P$1") (pinfunction "P$1_P$1") (pintype "bidirectional"))
      (node (ref "J11") (pin "6") (pinfunction "6_6") (pintype "passive"))
      (node (ref "J8") (pin "2") (pinfunction "2_2") (pintype "passive"))
      (node (ref "R46") (pin "1") (pinfunction "1_1") (pintype "passive"))
    )
    (net (code "43") (name "IN8N") (class "Default")
      (node (ref "ESD8") (pin "P$2") (pinfunction "P$2_P$2") (pintype "bidirectional"))
      (node (ref "J11") (pin "3") (pinfunction "3_3") (pintype "passive"))
      (node (ref "J9") (pin "3") (pinfunction "3_3") (pintype "passive"))
      (node (ref "R49") (pin "1") (pinfunction "1_1") (pintype "passive"))
    )
    (net (code "44") (name "IN8P") (class "Default")
      (node (ref "ESD8") (pin "P$1") (pinfunction "P$1_P$1") (pintype "bidirectional"))
      (node (ref "J11") (pin "4") (pinfunction "4_4") (pintype "passive"))
      (node (ref "J9") (pin "2") (pinfunction "2_2") (pintype "passive"))
      (node (ref "R48") (pin "1") (pinfunction "1_1") (pintype "passive"))
    )
    (net (code "45") (name "Net-(D1-PadA)") (class "Default")
      (node (ref "D1") (pin "A") (pinfunction "A_A") (pintype "passive"))
      (node (ref "R1") (pin "2") (pinfunction "2_2") (pintype "passive"))
    )
    (net (code "46") (name "Net-(D2-PadA)") (class "Default")
      (node (ref "D2") (pin "A") (pinfunction "A_A") (pintype "passive"))
      (node (ref "R18") (pin "2") (pinfunction "2_2") (pintype "passive"))
    )
    (net (code "47") (name "Net-(D3-PadA)") (class "Default")
      (node (ref "D3") (pin "A") (pinfunction "A_A") (pintype "passive"))
      (node (ref "R5") (pin "2") (pinfunction "2_2") (pintype "passive"))
    )
    (net (code "48") (name "Net-(D4-PadC)") (class "Default")
      (node (ref "D4") (pin "C") (pinfunction "C_C") (pintype "passive"))
      (node (ref "R8") (pin "2") (pinfunction "2_2") (pintype "passive"))
    )
    (net (code "49") (name "Net-(IC1-BIASIN)") (class "Default")
      (node (ref "IC1") (pin "62") (pinfunction "BIASIN_62") (pintype "input"))
      (node (ref "R21") (pin "1") (pinfunction "1_1") (pintype "passive"))
    )
    (net (code "50") (name "Net-(IC1-BIASOUT)") (class "Default")
      (node (ref "C43") (pin "1") (pinfunction "1_1") (pintype "passive"))
      (node (ref "IC1") (pin "63") (pinfunction "BIASOUT_63") (pintype "output"))
      (node (ref "R20") (pin "2") (pinfunction "2_2") (pintype "passive"))
    )
    (net (code "51") (name "Net-(IC1-VCAP1)") (class "Default")
      (node (ref "C17") (pin "1") (pinfunction "1_1") (pintype "passive"))
      (node (ref "IC1") (pin "28") (pinfunction "VCAP1_28") (pintype "bidirectional"))
    )
    (net (code "52") (name "Net-(IC1-VCAP2)") (class "Default")
      (node (ref "C18") (pin "1") (pinfunction "1_1") (pintype "passive"))
      (node (ref "IC1") (pin "30") (pinfunction "VCAP2_30") (pintype "bidirectional"))
    )
    (net (code "53") (name "Net-(IC1-VCAP3)") (class "Default")
      (node (ref "C19") (pin "1") (pinfunction "1_1") (pintype "passive"))
      (node (ref "C20") (pin "1") (pinfunction "1_1") (pintype "passive"))
      (node (ref "IC1") (pin "55") (pinfunction "VCAP3_55") (pintype "bidirectional"))
    )
    (net (code "54") (name "Net-(IC1-VCAP4)") (class "Default")
      (node (ref "C21") (pin "1") (pinfunction "1_1") (pintype "passive"))
      (node (ref "IC1") (pin "26") (pinfunction "VCAP4_26") (pintype "bidirectional"))
    )
    (net (code "55") (name "Net-(IC7-N_IN)") (class "Default")
      (node (ref "C26") (pin "2") (pinfunction "2_2") (pintype "passive"))
      (node (ref "C37") (pin "2") (pinfunction "2_2") (pintype "passive"))
      (node (ref "IC7") (pin "4") (pinfunction "N_IN_4") (pintype "bidirectional"))
      (node (ref "R11") (pin "1") (pinfunction "1_1") (pintype "passive"))
    )
    (net (code "56") (name "Net-(IC7-OUT)") (class "Default")
      (node (ref "C31") (pin "2") (pinfunction "2_2") (pintype "passive"))
      (node (ref "C37") (pin "1") (pinfunction "1_1") (pintype "passive"))
      (node (ref "IC7") (pin "1") (pinfunction "OUT_1") (pintype "bidirectional"))
      (node (ref "R10") (pin "1") (pinfunction "1_1") (pintype "passive"))
    )
    (net (code "57") (name "Net-(IC7-P_IN)") (class "Default")
      (node (ref "IC7") (pin "3") (pinfunction "P_IN_3") (pintype "bidirectional"))
      (node (ref "R22") (pin "1") (pinfunction "1_1") (pintype "passive"))
      (node (ref "R23") (pin "2") (pinfunction "2_2") (pintype "passive"))
    )
    (net (code "58") (name "Net-(ISO1-VIN+)") (class "Default")
      (node (ref "C3") (pin "1") (pinfunction "1_1") (pintype "passive"))
      (node (ref "ISO1") (pin "1") (pinfunction "VIN+_1") (pintype "input"))
      (node (ref "L1") (pin "2") (pinfunction "2_2") (pintype "passive"))
      (node (ref "U1") (pin "2") (pinfunction "+VIN_2") (pintype "passive"))
    )
    (net (code "59") (name "Net-(J11-Pad1)") (class "Default")
      (node (ref "J11") (pin "1") (pinfunction "1_1") (pintype "passive"))
      (node (ref "R6") (pin "1") (pinfunction "1_1") (pintype "passive"))
    )
    (net (code "60") (name "Net-(R3-Pad2)") (class "Default")
      (node (ref "R3") (pin "2") (pinfunction "2_2") (pintype "passive"))
      (node (ref "SJ4") (pin "2") (pinfunction "2_2") (pintype "passive"))
    )
    (net (code "61") (name "Net-(U2-IAUX)") (class "Default")
      (node (ref "R15") (pin "2") (pinfunction "2_2") (pintype "passive"))
      (node (ref "U2") (pin "16") (pinfunction "IAUX_16") (pintype "passive"))
    )
    (net (code "62") (name "Net-(U2-ISCLK)") (class "Default")
      (node (ref "R13") (pin "2") (pinfunction "2_2") (pintype "passive"))
      (node (ref "U2") (pin "14") (pinfunction "ISCLK_14") (pintype "passive"))
    )
    (net (code "63") (name "Net-(U2-ISDI)") (class "Default")
      (node (ref "R14") (pin "2") (pinfunction "2_2") (pintype "passive"))
      (node (ref "U2") (pin "15") (pinfunction "ISDI_15") (pintype "passive"))
    )
    (net (code "64") (name "Net-(U2-OSDO)") (class "Default")
      (node (ref "R16") (pin "2") (pinfunction "2_2") (pintype "passive"))
      (node (ref "U2") (pin "17") (pinfunction "OSDO_17") (pintype "passive"))
    )
    (net (code "65") (name "Net-(U2-SAA)") (class "Default")
      (node (ref "D4") (pin "A") (pinfunction "A_A") (pintype "passive"))
      (node (ref "U2") (pin "19") (pinfunction "SAA_19") (pintype "passive"))
    )
    (net (code "66") (name "Net-(U2-SBA)") (class "Default")
      (node (ref "R5") (pin "1") (pinfunction "1_1") (pintype "passive"))
      (node (ref "U2") (pin "9") (pinfunction "SBA_9") (pintype "passive"))
    )
    (net (code "67") (name "Net-(U2-~{ICS})") (class "Default")
      (node (ref "R12") (pin "2") (pinfunction "2_2") (pintype "passive"))
      (node (ref "U2") (pin "13") (pinfunction "~{ICS}_13") (pintype "passive"))
    )
    (net (code "68") (name "Net-(U2-~{OFAULT})") (class "Default")
      (node (ref "R17") (pin "2") (pinfunction "2_2") (pintype "passive"))
      (node (ref "U2") (pin "18") (pinfunction "~{OFAULT}_18") (pintype "passive"))
    )
    (net (code "69") (name "Net-(U2-~{SDOEN})") (class "Default")
      (node (ref "R7") (pin "2") (pinfunction "2_2") (pintype "passive"))
      (node (ref "U2") (pin "12") (pinfunction "~{SDOEN}_12") (pintype "passive"))
    )
    (net (code "70") (name "Net-(U3-VOUT)") (class "Default")
      (node (ref "C15") (pin "1") (pinfunction "1_1") (pintype "passive"))
      (node (ref "C16") (pin "1") (pinfunction "1_1") (pintype "passive"))
      (node (ref "L3") (pin "1") (pinfunction "1_1") (pintype "passive"))
      (node (ref "U3") (pin "5") (pinfunction "VOUT_5") (pintype "output"))
    )
    (net (code "71") (name "Net-(U4-VOUT)") (class "Default")
      (node (ref "C4") (pin "1") (pinfunction "1_1") (pintype "passive"))
      (node (ref "C5") (pin "1") (pinfunction "1_1") (pintype "passive"))
      (node (ref "L2") (pin "1") (pinfunction "1_1") (pintype "passive"))
      (node (ref "U4") (pin "5") (pinfunction "VOUT_5") (pintype "output"))
    )
    (net (code "72") (name "PE") (class "Default")
      (node (ref "C2") (pin "2") (pinfunction "2_2") (pintype "passive"))
      (node (ref "C3") (pin "2") (pinfunction "2_2") (pintype "passive"))
      (node (ref "C67") (pin "2") (pinfunction "2_2") (pintype "passive"))
      (node (ref "ISO1") (pin "2") (pinfunction "VIN-_2") (pintype "input"))
      (node (ref "JP26") (pin "6") (pinfunction "6_6") (pintype "passive"))
      (node (ref "JP26") (pin "7") (pinfunction "7_7") (pintype "passive"))
      (node (ref "R7") (pin "1") (pinfunction "1_1") (pintype "passive"))
      (node (ref "R8") (pin "1") (pinfunction "1_1") (pintype "passive"))
      (node (ref "U1") (pin "1") (pinfunction "-VIN_1") (pintype "passive"))
      (node (ref "U2") (pin "11") (pinfunction "GNDB_11") (pintype "passive"))
    )
    (net (code "73") (name "PGND") (class "Default")
      (node (ref "C26") (pin "1") (pinfunction "1_1") (pintype "passive"))
      (node (ref "C31") (pin "1") (pinfunction "1_1") (pintype "passive"))
      (node (ref "C32") (pin "2") (pinfunction "2_2") (pintype "passive"))
      (node (ref "J2") (pin "1") (pinfunction "1_1") (pintype "passive"))
      (node (ref "R10") (pin "2") (pinfunction "2_2") (pintype "passive"))
      (node (ref "R11") (pin "2") (pinfunction "2_2") (pintype "passive"))
      (node (ref "R21") (pin "2") (pinfunction "2_2") (pintype "passive"))
    )
    (net (code "74") (name "REF_ELEC") (class "Default")
      (node (ref "C62") (pin "1") (pinfunction "1_1") (pintype "passive"))
      (node (ref "IC8") (pin "3") (pinfunction "P_IN_3") (pintype "bidirectional"))
      (node (ref "R25") (pin "1") (pinfunction "1_1") (pintype "passive"))
    )
    (net (code "75") (name "REF_ELEC_CON") (class "Default")
      (node (ref "C35") (pin "1") (pinfunction "1_1") (pintype "passive"))
      (node (ref "J3") (pin "1") (pinfunction "1_1") (pintype "passive"))
      (node (ref "R25") (pin "2") (pinfunction "2_2") (pintype "passive"))
    )
    (net (code "76") (name "SPI2_CS") (class "Default")
      (node (ref "JP20") (pin "2") (pinfunction "2_2") (pintype "passive"))
      (node (ref "R12") (pin "1") (pinfunction "1_1") (pintype "passive"))
    )
    (net (code "77") (name "SPI2_MISO") (class "Default")
      (node (ref "JP25") (pin "5") (pinfunction "5_5") (pintype "passive"))
      (node (ref "R16") (pin "1") (pinfunction "1_1") (pintype "passive"))
    )
    (net (code "78") (name "SPI2_MOSI") (class "Default")
      (node (ref "JP25") (pin "3") (pinfunction "3_3") (pintype "passive"))
      (node (ref "R14") (pin "1") (pinfunction "1_1") (pintype "passive"))
    )
    (net (code "79") (name "SPI2_SCK") (class "Default")
      (node (ref "JP22") (pin "7") (pinfunction "7_7") (pintype "passive"))
      (node (ref "R13") (pin "1") (pinfunction "1_1") (pintype "passive"))
    )
    (net (code "80") (name "SPI_CLK") (class "Default")
      (node (ref "IC1") (pin "40") (pinfunction "SCLK_40") (pintype "input"))
      (node (ref "J1") (pin "5") (pinfunction "5_5") (pintype "passive"))
      (node (ref "U2") (pin "7") (pinfunction "OSCLK_7") (pintype "passive"))
    )
    (net (code "81") (name "SPI_IN") (class "Default")
      (node (ref "IC1") (pin "34") (pinfunction "DIN_34") (pintype "input"))
      (node (ref "J1") (pin "6") (pinfunction "6_6") (pintype "passive"))
      (node (ref "U2") (pin "6") (pinfunction "OSDI_6") (pintype "passive"))
    )
    (net (code "82") (name "SPI_OUT") (class "Default")
      (node (ref "IC1") (pin "43") (pinfunction "DOUT_43") (pintype "output"))
      (node (ref "J1") (pin "8") (pinfunction "8_8") (pintype "passive"))
      (node (ref "U2") (pin "4") (pinfunction "ISDO_4") (pintype "passive"))
    )
    (net (code "83") (name "SRB1") (class "Default")
      (node (ref "IC1") (pin "17") (pinfunction "SRB1_17") (pintype "output"))
      (node (ref "IC8") (pin "1") (pinfunction "OUT_1") (pintype "bidirectional"))
      (node (ref "IC8") (pin "4") (pinfunction "N_IN_4") (pintype "bidirectional"))
    )
    (net (code "84") (name "SRB2") (class "Default")
      (node (ref "IC1") (pin "18") (pinfunction "SRB2_18") (pintype "output"))
      (node (ref "J1") (pin "10") (pinfunction "10_10") (pintype "passive"))
    )
    (net (code "85") (name "START") (class "Default")
      (node (ref "IC1") (pin "38") (pinfunction "START_38") (pintype "input"))
      (node (ref "J1") (pin "7") (pinfunction "7_7") (pintype "passive"))
      (node (ref "U2") (pin "5") (pinfunction "OAUX_5") (pintype "passive"))
    )
    (net (code "86") (name "START_D68") (class "Default")
      (node (ref "JP24") (pin "2") (pinfunction "2_2") (pintype "passive"))
      (node (ref "R15") (pin "1") (pinfunction "1_1") (pintype "passive"))
    )
    (net (code "87") (name "VCC_5V") (class "Default")
      (node (ref "C27") (pin "1") (pinfunction "1_1") (pintype "passive"))
      (node (ref "C28") (pin "1") (pinfunction "1_1") (pintype "passive"))
      (node (ref "ISO1") (pin "7") (pinfunction "VOUT+_7") (pintype "output"))
      (node (ref "J1") (pin "2") (pinfunction "2_2") (pintype "passive"))
      (node (ref "L4") (pin "1") (pinfunction "1_1") (pintype "passive"))
      (node (ref "U1") (pin "5") (pinfunction "+VOUT_5") (pintype "passive"))
    )
    (net (code "88") (name "VCC_5V_FILTERED") (class "Default")
      (node (ref "C1") (pin "1") (pinfunction "1_1") (pintype "passive"))
      (node (ref "C64") (pin "1") (pinfunction "1_1") (pintype "passive"))
      (node (ref "C65") (pin "1") (pinfunction "1_1") (pintype "passive"))
      (node (ref "C68") (pin "1") (pinfunction "1_1") (pintype "passive"))
      (node (ref "L4") (pin "2") (pinfunction "2_2") (pintype "passive"))
      (node (ref "U3") (pin "1") (pinfunction "VIN_1") (pintype "input"))
      (node (ref "U3") (pin "3") (pinfunction "EN_3") (pintype "input"))
      (node (ref "U4") (pin "1") (pinfunction "VIN_1") (pintype "input"))
      (node (ref "U4") (pin "3") (pinfunction "EN_3") (pintype "input"))
    )
    (net (code "89") (name "VCC_MCU") (class "Default")
      (node (ref "C2") (pin "1") (pinfunction "1_1") (pintype "passive"))
      (node (ref "C67") (pin "1") (pinfunction "1_1") (pintype "passive"))
      (node (ref "JP26") (pin "5") (pinfunction "5_5") (pintype "passive"))
      (node (ref "L1") (pin "1") (pinfunction "1_1") (pintype "passive"))
      (node (ref "U2") (pin "20") (pinfunction "VDDB_20") (pintype "power_in"))
    )
    (net (code "90") (name "VREFP") (class "Default")
      (node (ref "C22") (pin "1") (pinfunction "1_1") (pintype "passive"))
      (node (ref "C23") (pin "1") (pinfunction "1_1") (pintype "passive"))
      (node (ref "IC1") (pin "24") (pinfunction "VREFP_24") (pintype "bidirectional"))
      (node (ref "TP4") (pin "1") (pinfunction "1_1") (pintype "passive"))
    )
    (net (code "91") (name "unconnected-(IC1-BIASREF-Pad60)") (class "Default")
      (node (ref "IC1") (pin "60") (pinfunction "BIASREF_60") (pintype "input"))
    )
    (net (code "92") (name "unconnected-(IC1-NC-Pad27)") (class "Default")
      (node (ref "IC1") (pin "27") (pinfunction "NC_27") (pintype "no_connect"))
    )
    (net (code "93") (name "unconnected-(IC1-NC-Pad29)") (class "Default")
      (node (ref "IC1") (pin "29") (pinfunction "NC_29") (pintype "no_connect"))
    )
    (net (code "94") (name "unconnected-(IC1-NC-Pad64)") (class "Default")
      (node (ref "IC1") (pin "64") (pinfunction "NC_64") (pintype "no_connect"))
    )
    (net (code "95") (name "unconnected-(IC1-RESV1-Pad31)") (class "Default")
      (node (ref "IC1") (pin "31") (pinfunction "RESV1_31") (pintype "no_connect"))
    )
    (net (code "96") (name "unconnected-(ISO1-NC-Pad6)") (class "Default")
      (node (ref "ISO1") (pin "6") (pinfunction "NC_6") (pintype "no_connect"))
    )
    (net (code "97") (name "unconnected-(J2-Pad4)") (class "Default")
      (node (ref "J2") (pin "4") (pinfunction "4_4") (pintype "passive"))
    )
    (net (code "98") (name "unconnected-(J2-Pad5)") (class "Default")
      (node (ref "J2") (pin "5") (pinfunction "5_5") (pintype "passive"))
    )
    (net (code "99") (name "unconnected-(J3-Pad4)") (class "Default")
      (node (ref "J3") (pin "4") (pinfunction "4_4") (pintype "passive"))
    )
    (net (code "100") (name "unconnected-(J3-Pad5)") (class "Default")
      (node (ref "J3") (pin "5") (pinfunction "5_5") (pintype "passive"))
    )
    (net (code "101") (name "unconnected-(J4-Pad1)") (class "Default")
      (node (ref "J4") (pin "1") (pinfunction "1_1") (pintype "passive"))
    )
    (net (code "102") (name "unconnected-(J4-Pad4)") (class "Default")
      (node (ref "J4") (pin "4") (pinfunction "4_4") (pintype "passive"))
    )
    (net (code "103") (name "unconnected-(J4-Pad5)") (class "Default")
      (node (ref "J4") (pin "5") (pinfunction "5_5") (pintype "passive"))
    )
    (net (code "104") (name "unconnected-(J5-Pad1)") (class "Default")
      (node (ref "J5") (pin "1") (pinfunction "1_1") (pintype "passive"))
    )
    (net (code "105") (name "unconnected-(J5-Pad4)") (class "Default")
      (node (ref "J5") (pin "4") (pinfunction "4_4") (pintype "passive"))
    )
    (net (code "106") (name "unconnected-(J5-Pad5)") (class "Default")
      (node (ref "J5") (pin "5") (pinfunction "5_5") (pintype "passive"))
    )
    (net (code "107") (name "unconnected-(J6-Pad1)") (class "Default")
      (node (ref "J6") (pin "1") (pinfunction "1_1") (pintype "passive"))
    )
    (net (code "108") (name "unconnected-(J6-Pad4)") (class "Default")
      (node (ref "J6") (pin "4") (pinfunction "4_4") (pintype "passive"))
    )
    (net (code "109") (name "unconnected-(J6-Pad5)") (class "Default")
      (node (ref "J6") (pin "5") (pinfunction "5_5") (pintype "passive"))
    )
    (net (code "110") (name "unconnected-(J7-Pad1)") (class "Default")
      (node (ref "J7") (pin "1") (pinfunction "1_1") (pintype "passive"))
    )
    (net (code "111") (name "unconnected-(J7-Pad4)") (class "Default")
      (node (ref "J7") (pin "4") (pinfunction "4_4") (pintype "passive"))
    )
    (net (code "112") (name "unconnected-(J7-Pad5)") (class "Default")
      (node (ref "J7") (pin "5") (pinfunction "5_5") (pintype "passive"))
    )
    (net (code "113") (name "unconnected-(J8-Pad1)") (class "Default")
      (node (ref "J8") (pin "1") (pinfunction "1_1") (pintype "passive"))
    )
    (net (code "114") (name "unconnected-(J8-Pad4)") (class "Default")
      (node (ref "J8") (pin "4") (pinfunction "4_4") (pintype "passive"))
    )
    (net (code "115") (name "unconnected-(J8-Pad5)") (class "Default")
      (node (ref "J8") (pin "5") (pinfunction "5_5") (pintype "passive"))
    )
    (net (code "116") (name "unconnected-(J9-Pad1)") (class "Default")
      (node (ref "J9") (pin "1") (pinfunction "1_1") (pintype "passive"))
    )
    (net (code "117") (name "unconnected-(J9-Pad4)") (class "Default")
      (node (ref "J9") (pin "4") (pinfunction "4_4") (pintype "passive"))
    )
    (net (code "118") (name "unconnected-(J9-Pad5)") (class "Default")
      (node (ref "J9") (pin "5") (pinfunction "5_5") (pintype "passive"))
    )
    (net (code "119") (name "unconnected-(J11-Pad2)") (class "Default")
      (node (ref "J11") (pin "2") (pinfunction "2_2") (pintype "passive"))
    )
    (net (code "120") (name "unconnected-(JP20-Pad1)") (class "Default")
      (node (ref "JP20") (pin "1") (pinfunction "1_1") (pintype "passive"))
    )
    (net (code "121") (name "unconnected-(JP20-Pad3)") (class "Default")
      (node (ref "JP20") (pin "3") (pinfunction "3_3") (pintype "passive"))
    )
    (net (code "122") (name "unconnected-(JP20-Pad4)") (class "Default")
      (node (ref "JP20") (pin "4") (pinfunction "4_4") (pintype "passive"))
    )
    (net (code "123") (name "unconnected-(JP20-Pad5)") (class "Default")
      (node (ref "JP20") (pin "5") (pinfunction "5_5") (pintype "passive"))
    )
    (net (code "124") (name "unconnected-(JP20-Pad6)") (class "Default")
      (node (ref "JP20") (pin "6") (pinfunction "6_6") (pintype "passive"))
    )
    (net (code "125") (name "unconnected-(JP20-Pad7)") (class "Default")
      (node (ref "JP20") (pin "7") (pinfunction "7_7") (pintype "passive"))
    )
    (net (code "126") (name "unconnected-(JP20-Pad8)") (class "Default")
      (node (ref "JP20") (pin "8") (pinfunction "8_8") (pintype "passive"))
    )
    (net (code "127") (name "unconnected-(JP20-Pad9)") (class "Default")
      (node (ref "JP20") (pin "9") (pinfunction "9_9") (pintype "passive"))
    )
    (net (code "128") (name "unconnected-(JP20-Pad10)") (class "Default")
      (node (ref "JP20") (pin "10") (pinfunction "10_10") (pintype "passive"))
    )
    (net (code "129") (name "unconnected-(JP21-Pad1)") (class "Default")
      (node (ref "JP21") (pin "1") (pinfunction "1_1") (pintype "passive"))
    )
    (net (code "130") (name "unconnected-(JP21-Pad2)") (class "Default")
      (node (ref "JP21") (pin "2") (pinfunction "2_2") (pintype "passive"))
    )
    (net (code "131") (name "unconnected-(JP21-Pad3)") (class "Default")
      (node (ref "JP21") (pin "3") (pinfunction "3_3") (pintype "passive"))
    )
    (net (code "132") (name "unconnected-(JP21-Pad4)") (class "Default")
      (node (ref "JP21") (pin "4") (pinfunction "4_4") (pintype "passive"))
    )
    (net (code "133") (name "unconnected-(JP21-Pad5)") (class "Default")
      (node (ref "JP21") (pin "5") (pinfunction "5_5") (pintype "passive"))
    )
    (net (code "134") (name "unconnected-(JP21-Pad6)") (class "Default")
      (node (ref "JP21") (pin "6") (pinfunction "6_6") (pintype "passive"))
    )
    (net (code "135") (name "unconnected-(JP21-Pad7)") (class "Default")
      (node (ref "JP21") (pin "7") (pinfunction "7_7") (pintype "passive"))
    )
    (net (code "136") (name "unconnected-(JP21-Pad8)") (class "Default")
      (node (ref "JP21") (pin "8") (pinfunction "8_8") (pintype "passive"))
    )
    (net (code "137") (name "unconnected-(JP22-Pad1)") (class "Default")
      (node (ref "JP22") (pin "1") (pinfunction "1_1") (pintype "passive"))
    )
    (net (code "138") (name "unconnected-(JP22-Pad2)") (class "Default")
      (node (ref "JP22") (pin "2") (pinfunction "2_2") (pintype "passive"))
    )
    (net (code "139") (name "unconnected-(JP22-Pad3)") (class "Default")
      (node (ref "JP22") (pin "3") (pinfunction "3_3") (pintype "passive"))
    )
    (net (code "140") (name "unconnected-(JP22-Pad4)") (class "Default")
      (node (ref "JP22") (pin "4") (pinfunction "4_4") (pintype "passive"))
    )
    (net (code "141") (name "unconnected-(JP22-Pad5)") (class "Default")
      (node (ref "JP22") (pin "5") (pinfunction "5_5") (pintype "passive"))
    )
    (net (code "142") (name "unconnected-(JP22-Pad6)") (class "Default")
      (node (ref "JP22") (pin "6") (pinfunction "6_6") (pintype "passive"))
    )
    (net (code "143") (name "unconnected-(JP22-Pad8)") (class "Default")
      (node (ref "JP22") (pin "8") (pinfunction "8_8") (pintype "passive"))
    )
    (net (code "144") (name "unconnected-(JP24-Pad3)") (class "Default")
      (node (ref "JP24") (pin "3") (pinfunction "3_3") (pintype "passive"))
    )
    (net (code "145") (name "unconnected-(JP24-Pad4)") (class "Default")
      (node (ref "JP24") (pin "4") (pinfunction "4_4") (pintype "passive"))
    )
    (net (code "146") (name "unconnected-(JP24-Pad5)") (class "Default")
      (node (ref "JP24") (pin "5") (pinfunction "5_5") (pintype "passive"))
    )
    (net (code "147") (name "unconnected-(JP24-Pad6)") (class "Default")
      (node (ref "JP24") (pin "6") (pinfunction "6_6") (pintype "passive"))
    )
    (net (code "148") (name "unconnected-(JP24-Pad7)") (class "Default")
      (node (ref "JP24") (pin "7") (pinfunction "7_7") (pintype "passive"))
    )
    (net (code "149") (name "unconnected-(JP24-Pad8)") (class "Default")
      (node (ref "JP24") (pin "8") (pinfunction "8_8") (pintype "passive"))
    )
    (net (code "150") (name "unconnected-(JP25-Pad1)") (class "Default")
      (node (ref "JP25") (pin "1") (pinfunction "1_1") (pintype "passive"))
    )
    (net (code "151") (name "unconnected-(JP25-Pad2)") (class "Default")
      (node (ref "JP25") (pin "2") (pinfunction "2_2") (pintype "passive"))
    )
    (net (code "152") (name "unconnected-(JP25-Pad4)") (class "Default")
      (node (ref "JP25") (pin "4") (pinfunction "4_4") (pintype "passive"))
    )
    (net (code "153") (name "unconnected-(JP25-Pad6)") (class "Default")
      (node (ref "JP25") (pin "6") (pinfunction "6_6") (pintype "passive"))
    )
    (net (code "154") (name "unconnected-(JP25-Pad7)") (class "Default")
      (node (ref "JP25") (pin "7") (pinfunction "7_7") (pintype "passive"))
    )
    (net (code "155") (name "unconnected-(JP25-Pad8)") (class "Default")
      (node (ref "JP25") (pin "8") (pinfunction "8_8") (pintype "passive"))
    )
    (net (code "156") (name "unconnected-(JP26-Pad1)") (class "Default")
      (node (ref "JP26") (pin "1") (pinfunction "1_1") (pintype "passive"))
    )
    (net (code "157") (name "unconnected-(JP26-Pad2)") (class "Default")
      (node (ref "JP26") (pin "2") (pinfunction "2_2") (pintype "passive"))
    )
    (net (code "158") (name "unconnected-(JP26-Pad3)") (class "Default")
      (node (ref "JP26") (pin "3") (pinfunction "3_3") (pintype "passive"))
    )
    (net (code "159") (name "unconnected-(JP26-Pad4)") (class "Default")
      (node (ref "JP26") (pin "4") (pinfunction "4_4") (pintype "passive"))
    )
    (net (code "160") (name "unconnected-(JP26-Pad8)") (class "Default")
      (node (ref "JP26") (pin "8") (pinfunction "8_8") (pintype "passive"))
    )
    (net (code "161") (name "unconnected-(U1-NC-Pad8)") (class "Default")
      (node (ref "U1") (pin "8") (pinfunction "NC_8") (pintype "no_connect"))
    )
    (net (code "162") (name "unconnected-(U3-NC-Pad4)") (class "Default")
      (node (ref "U3") (pin "4") (pinfunction "NC_4") (pintype "no_connect"))
    )
    (net (code "163") (name "unconnected-(U4-NC-Pad4)") (class "Default")
      (node (ref "U4") (pin "4") (pinfunction "NC_4") (pintype "no_connect"))
    )
    (net (code "164") (name "~{PWDN}") (class "Default")
      (node (ref "C41") (pin "1") (pinfunction "1_1") (pintype "passive"))
      (node (ref "IC1") (pin "35") (pinfunction "~{PWDN}_35") (pintype "input"))
      (node (ref "R4") (pin "1") (pinfunction "1_1") (pintype "passive"))
      (node (ref "SW1") (pin "A") (pinfunction "P_A") (pintype "passive"))
      (node (ref "SW1") (pin "A'") (pinfunction "P1_A'") (pintype "passive"))
    )
    (net (code "165") (name "~{RESET}") (class "Default")
      (node (ref "C39") (pin "1") (pinfunction "1_1") (pintype "passive"))
      (node (ref "IC1") (pin "36") (pinfunction "~{RESET}_36") (pintype "input"))
      (node (ref "R9") (pin "1") (pinfunction "1_1") (pintype "passive"))
    )
    (net (code "166") (name "~{SPI_CS}") (class "Default")
      (node (ref "IC1") (pin "39") (pinfunction "~{CS}_39") (pintype "input"))
      (node (ref "J1") (pin "4") (pinfunction "4_4") (pintype "passive"))
      (node (ref "R2") (pin "2") (pinfunction "2_2") (pintype "passive"))
      (node (ref "U2") (pin "8") (pinfunction "~{OCS}_8") (pintype "passive"))
    )
  )
)
